# HDMI_RGB_LVDS_fertig_V4.net
KiCad netlist of a schematic drawn in EAGLE
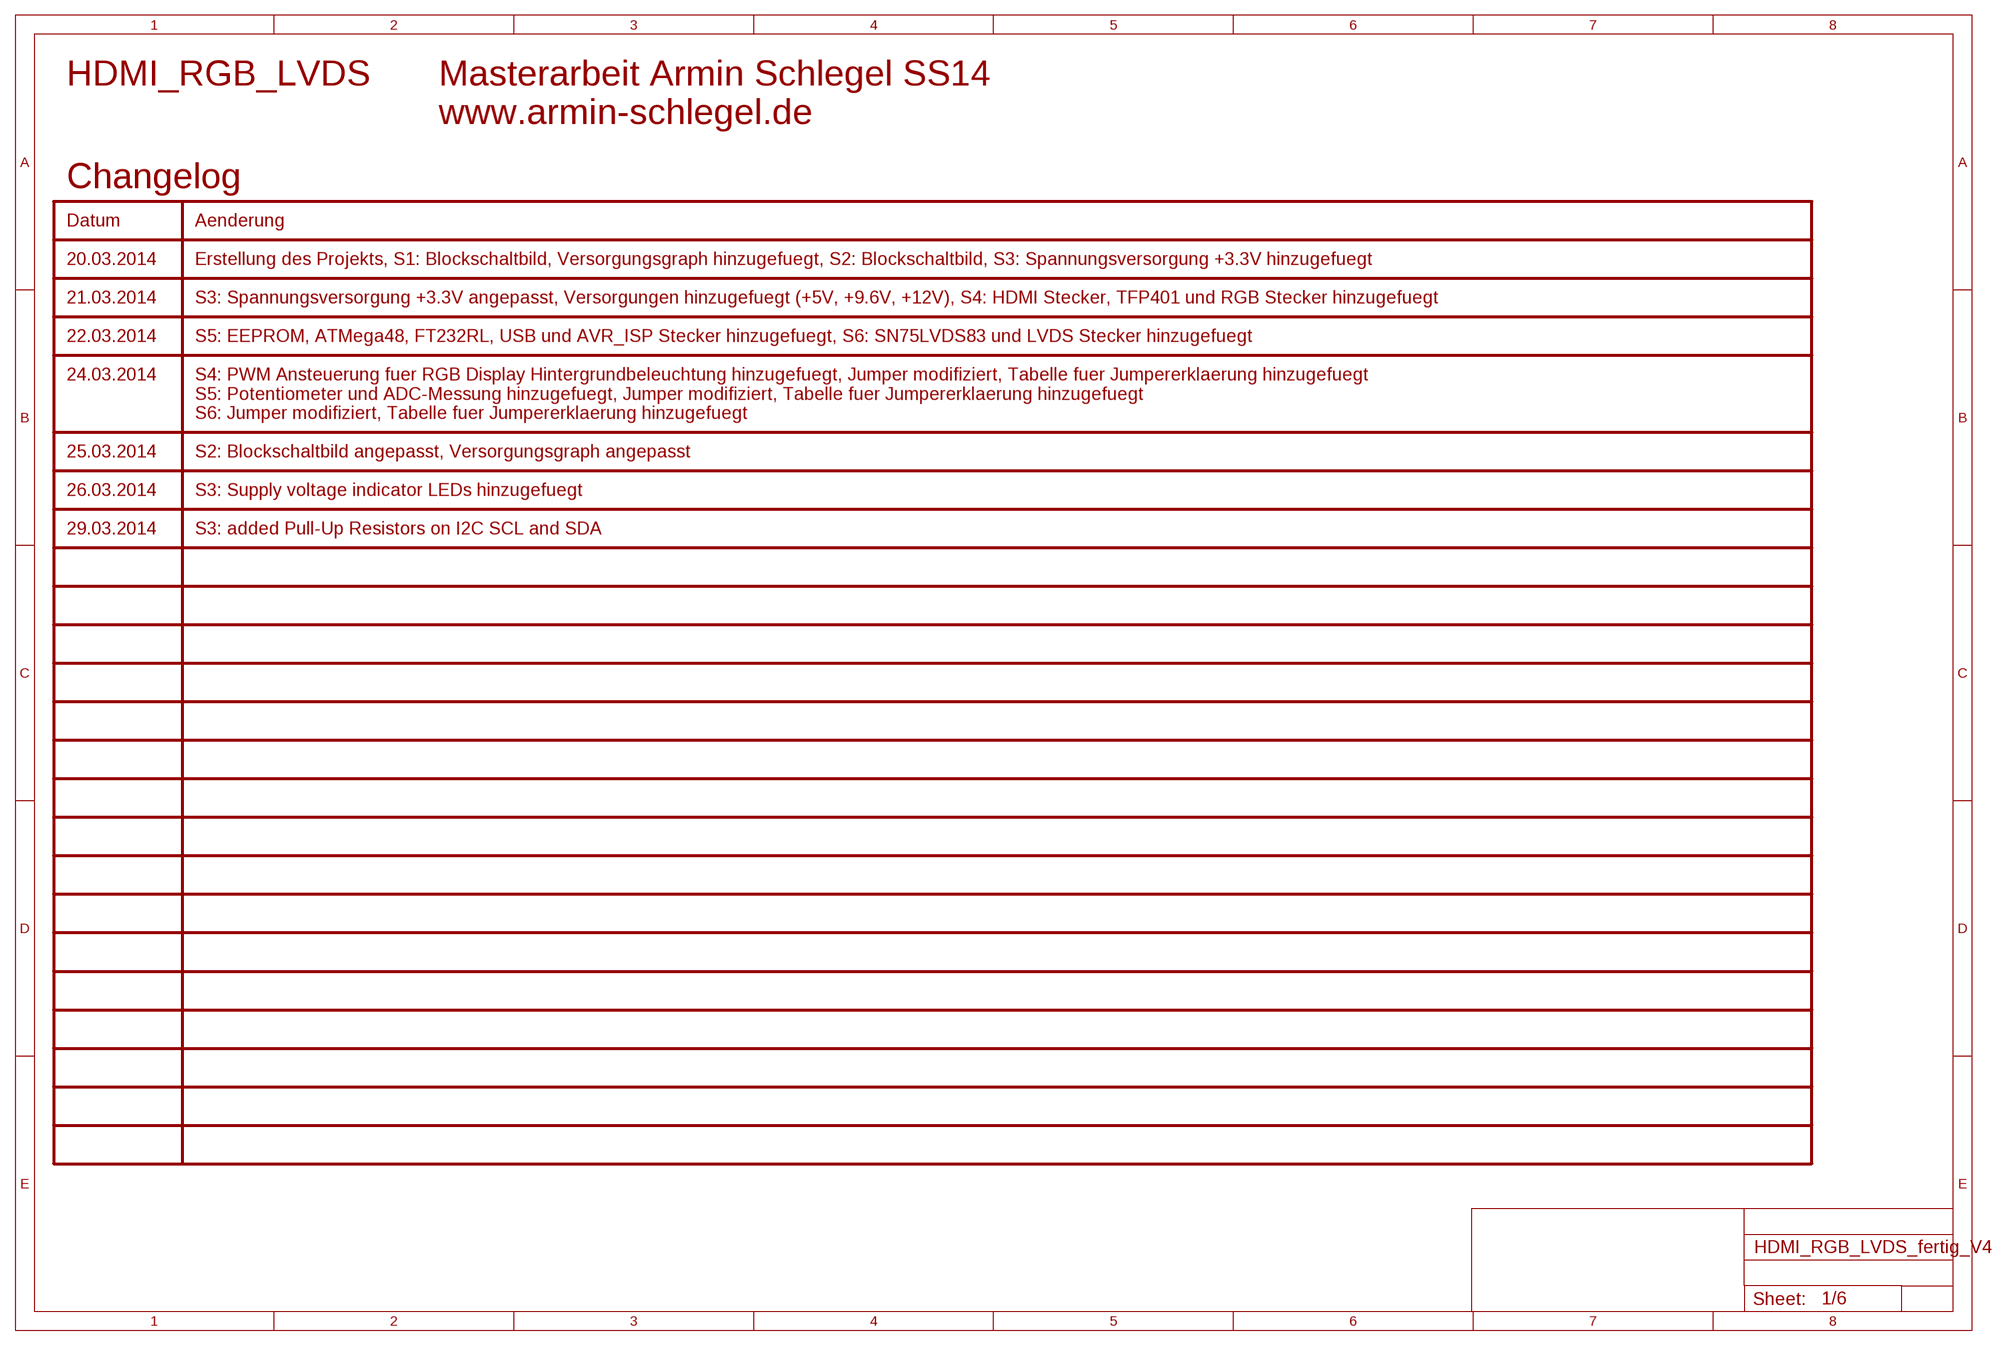
[diagram p0: schematic, sheet 1]
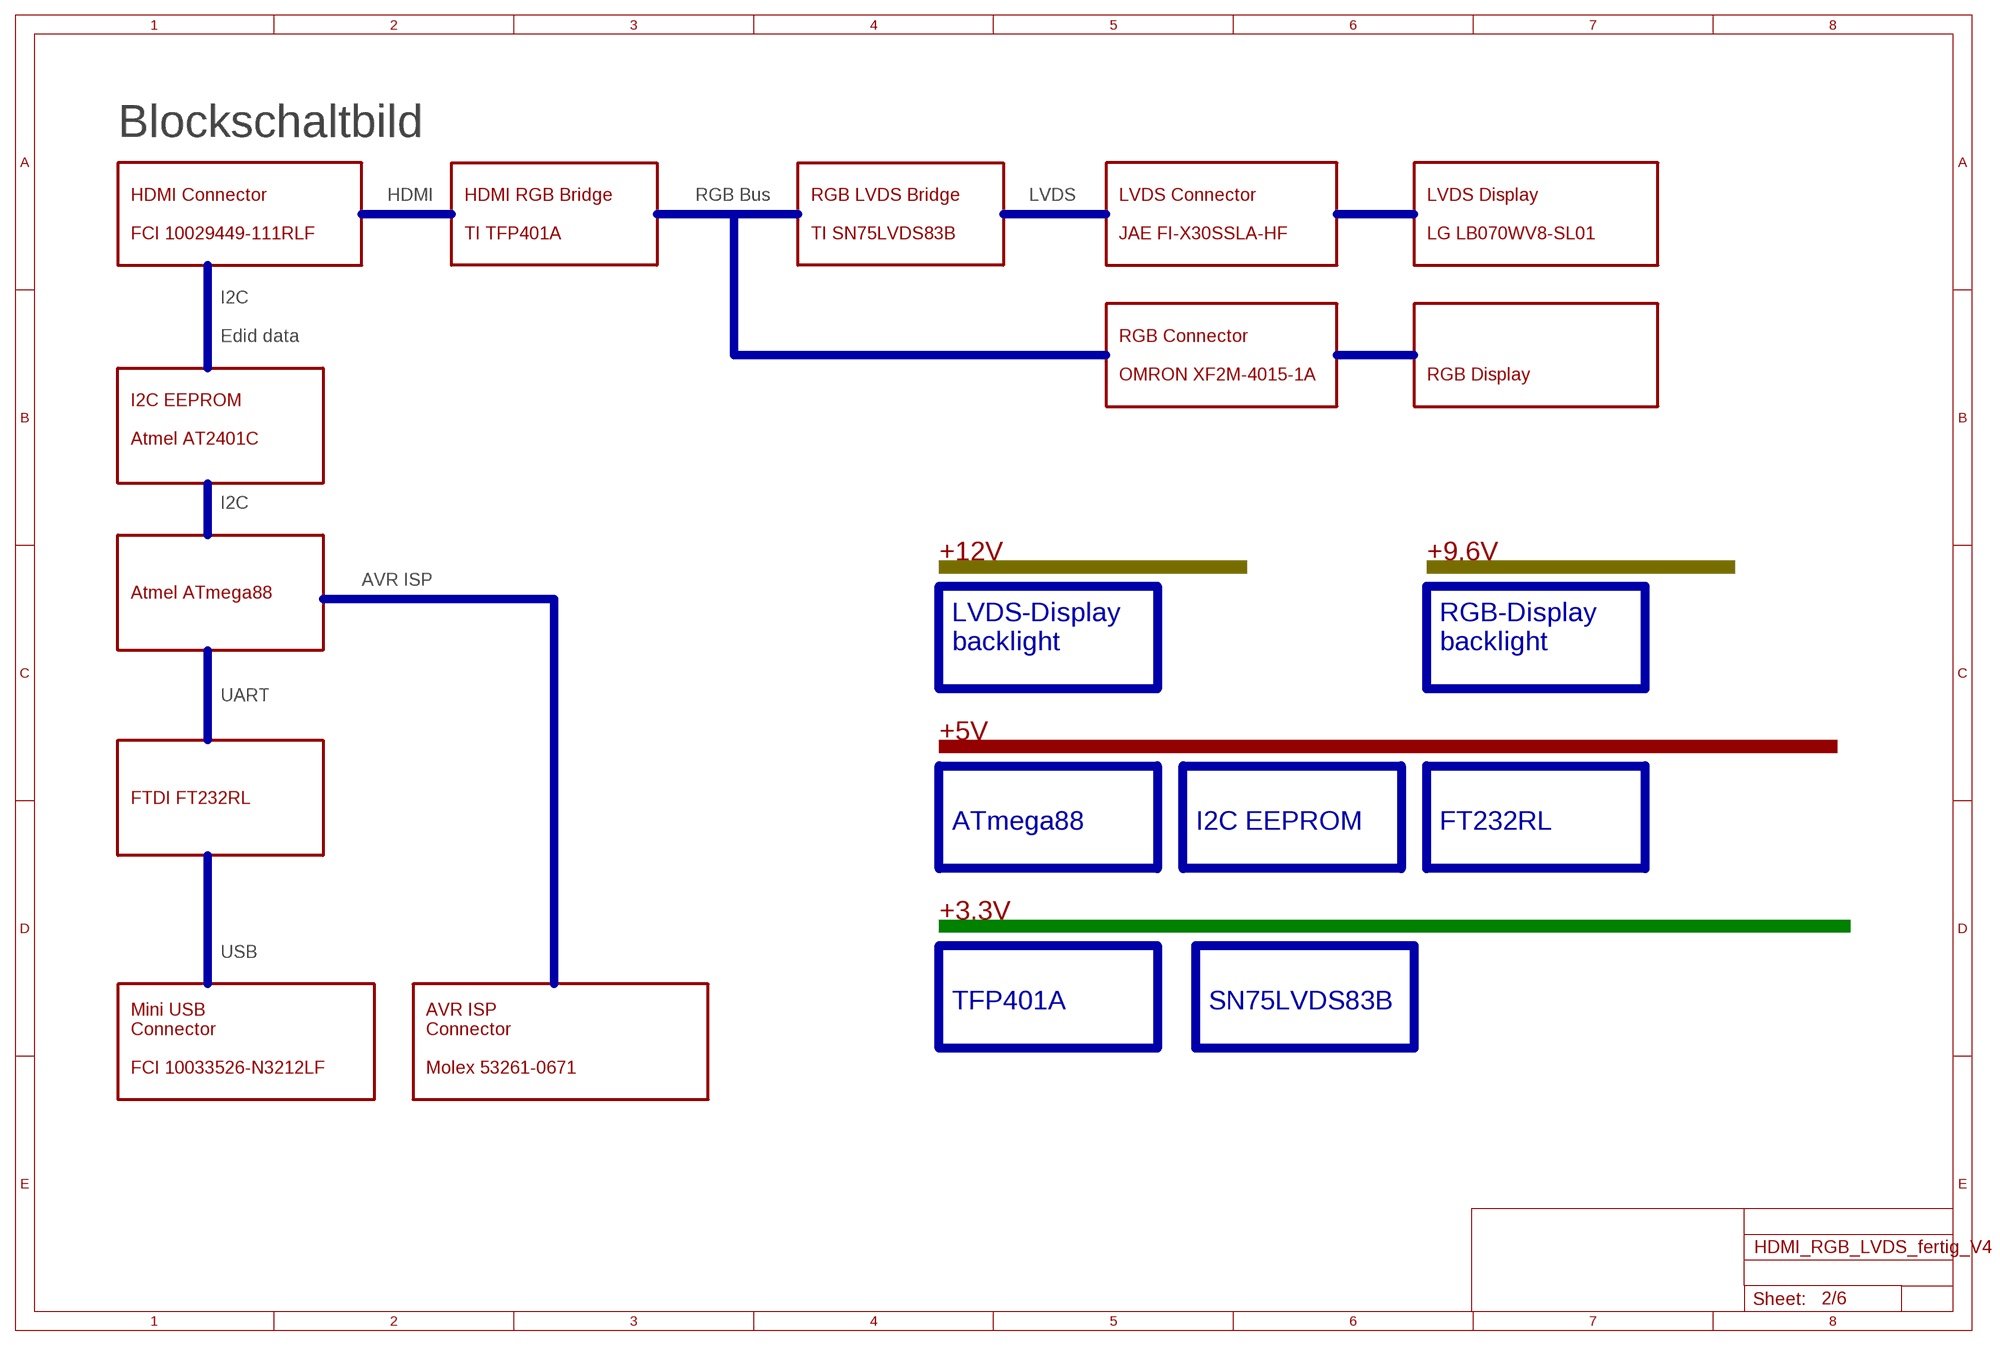
[diagram p1: schematic, sheet 2]
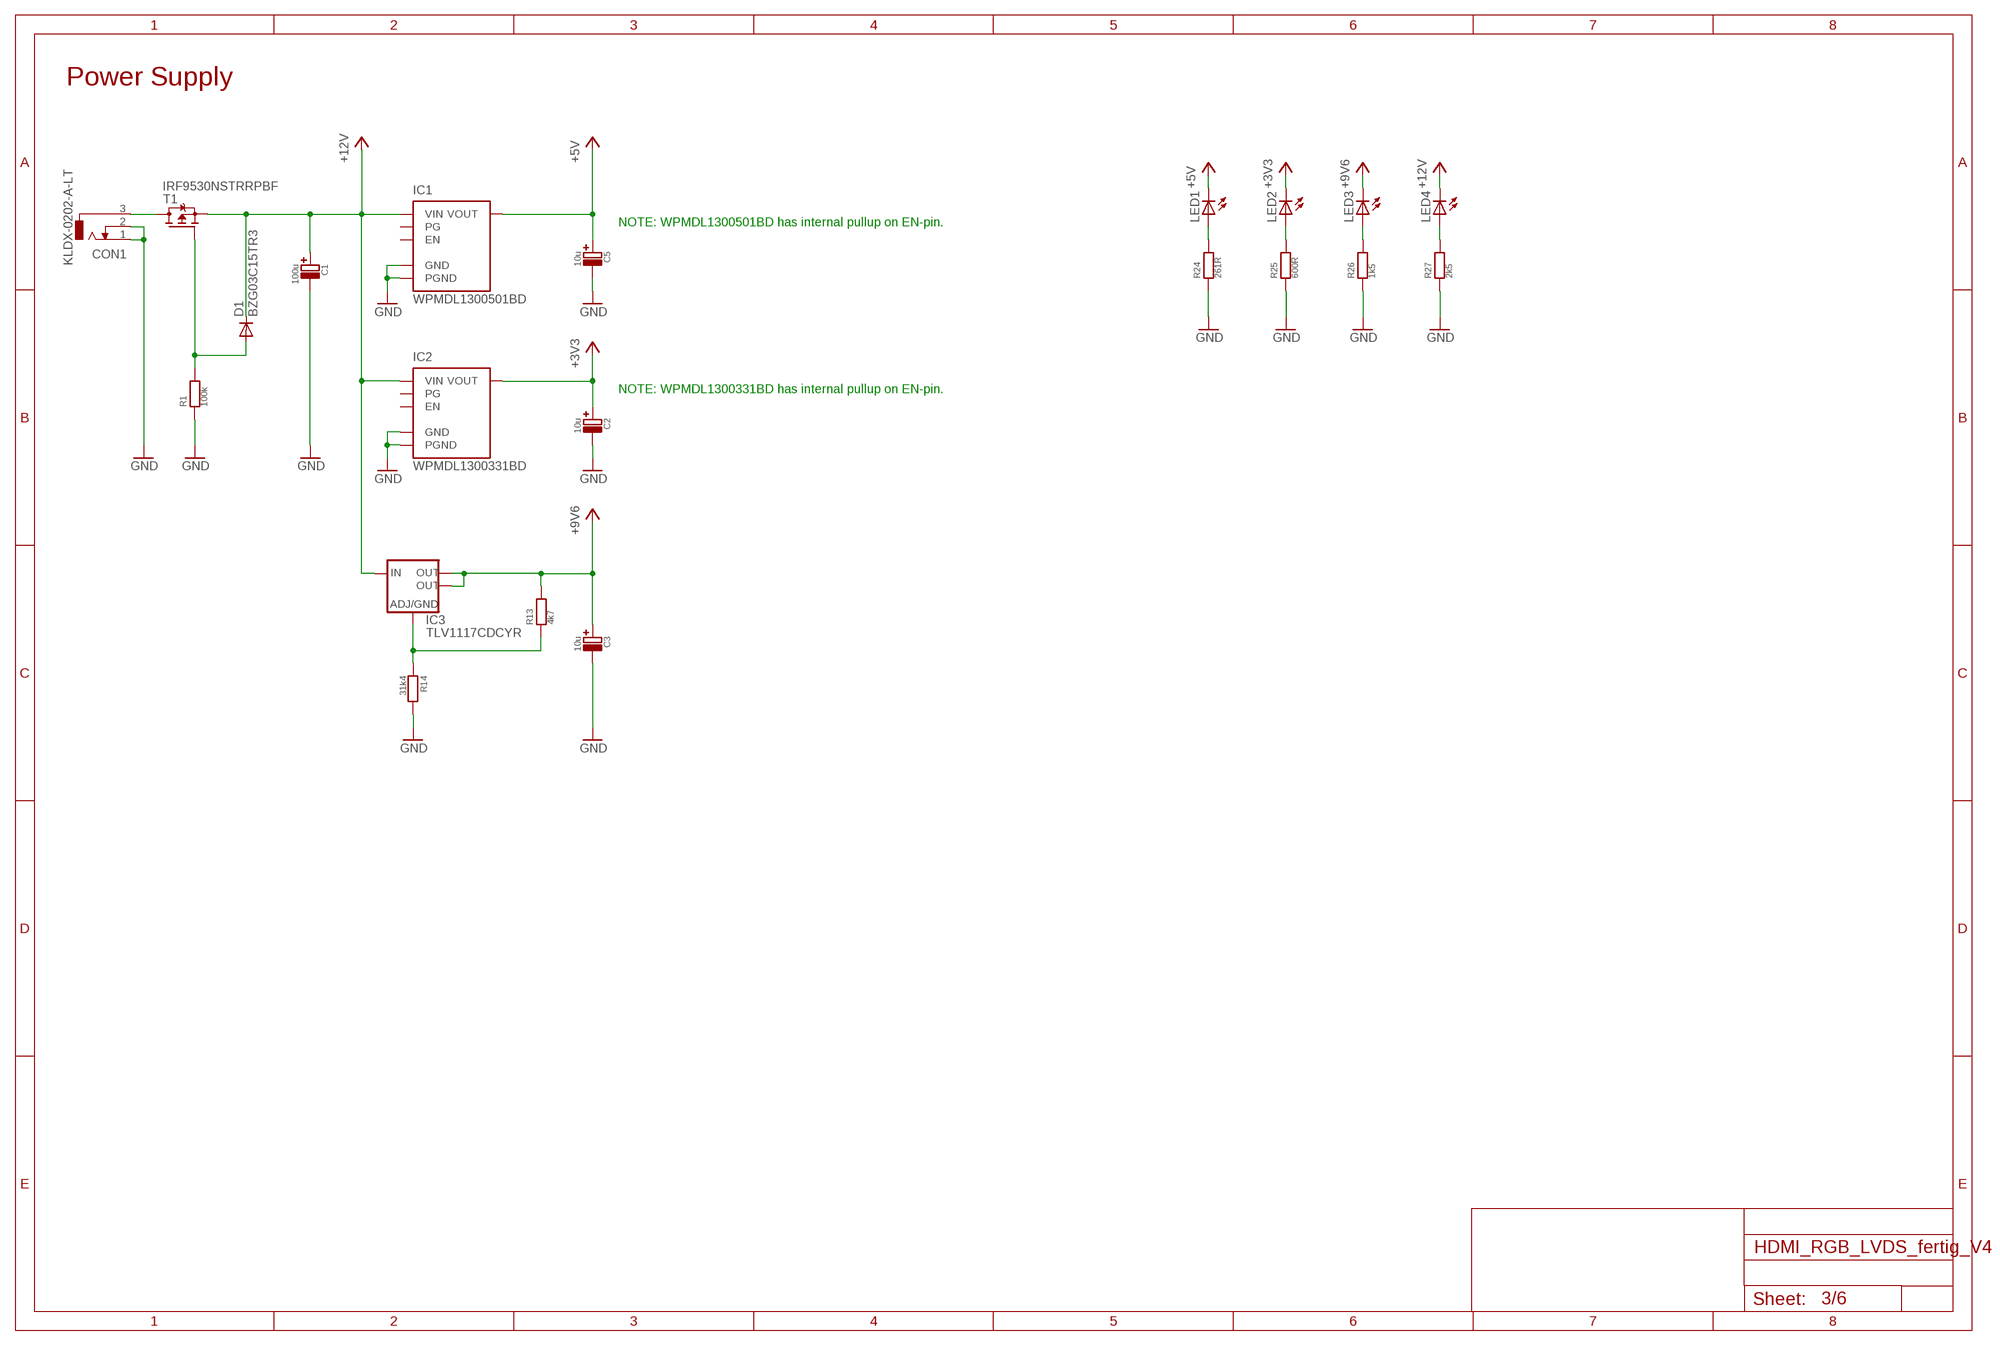
[diagram p2: schematic, sheet 3]
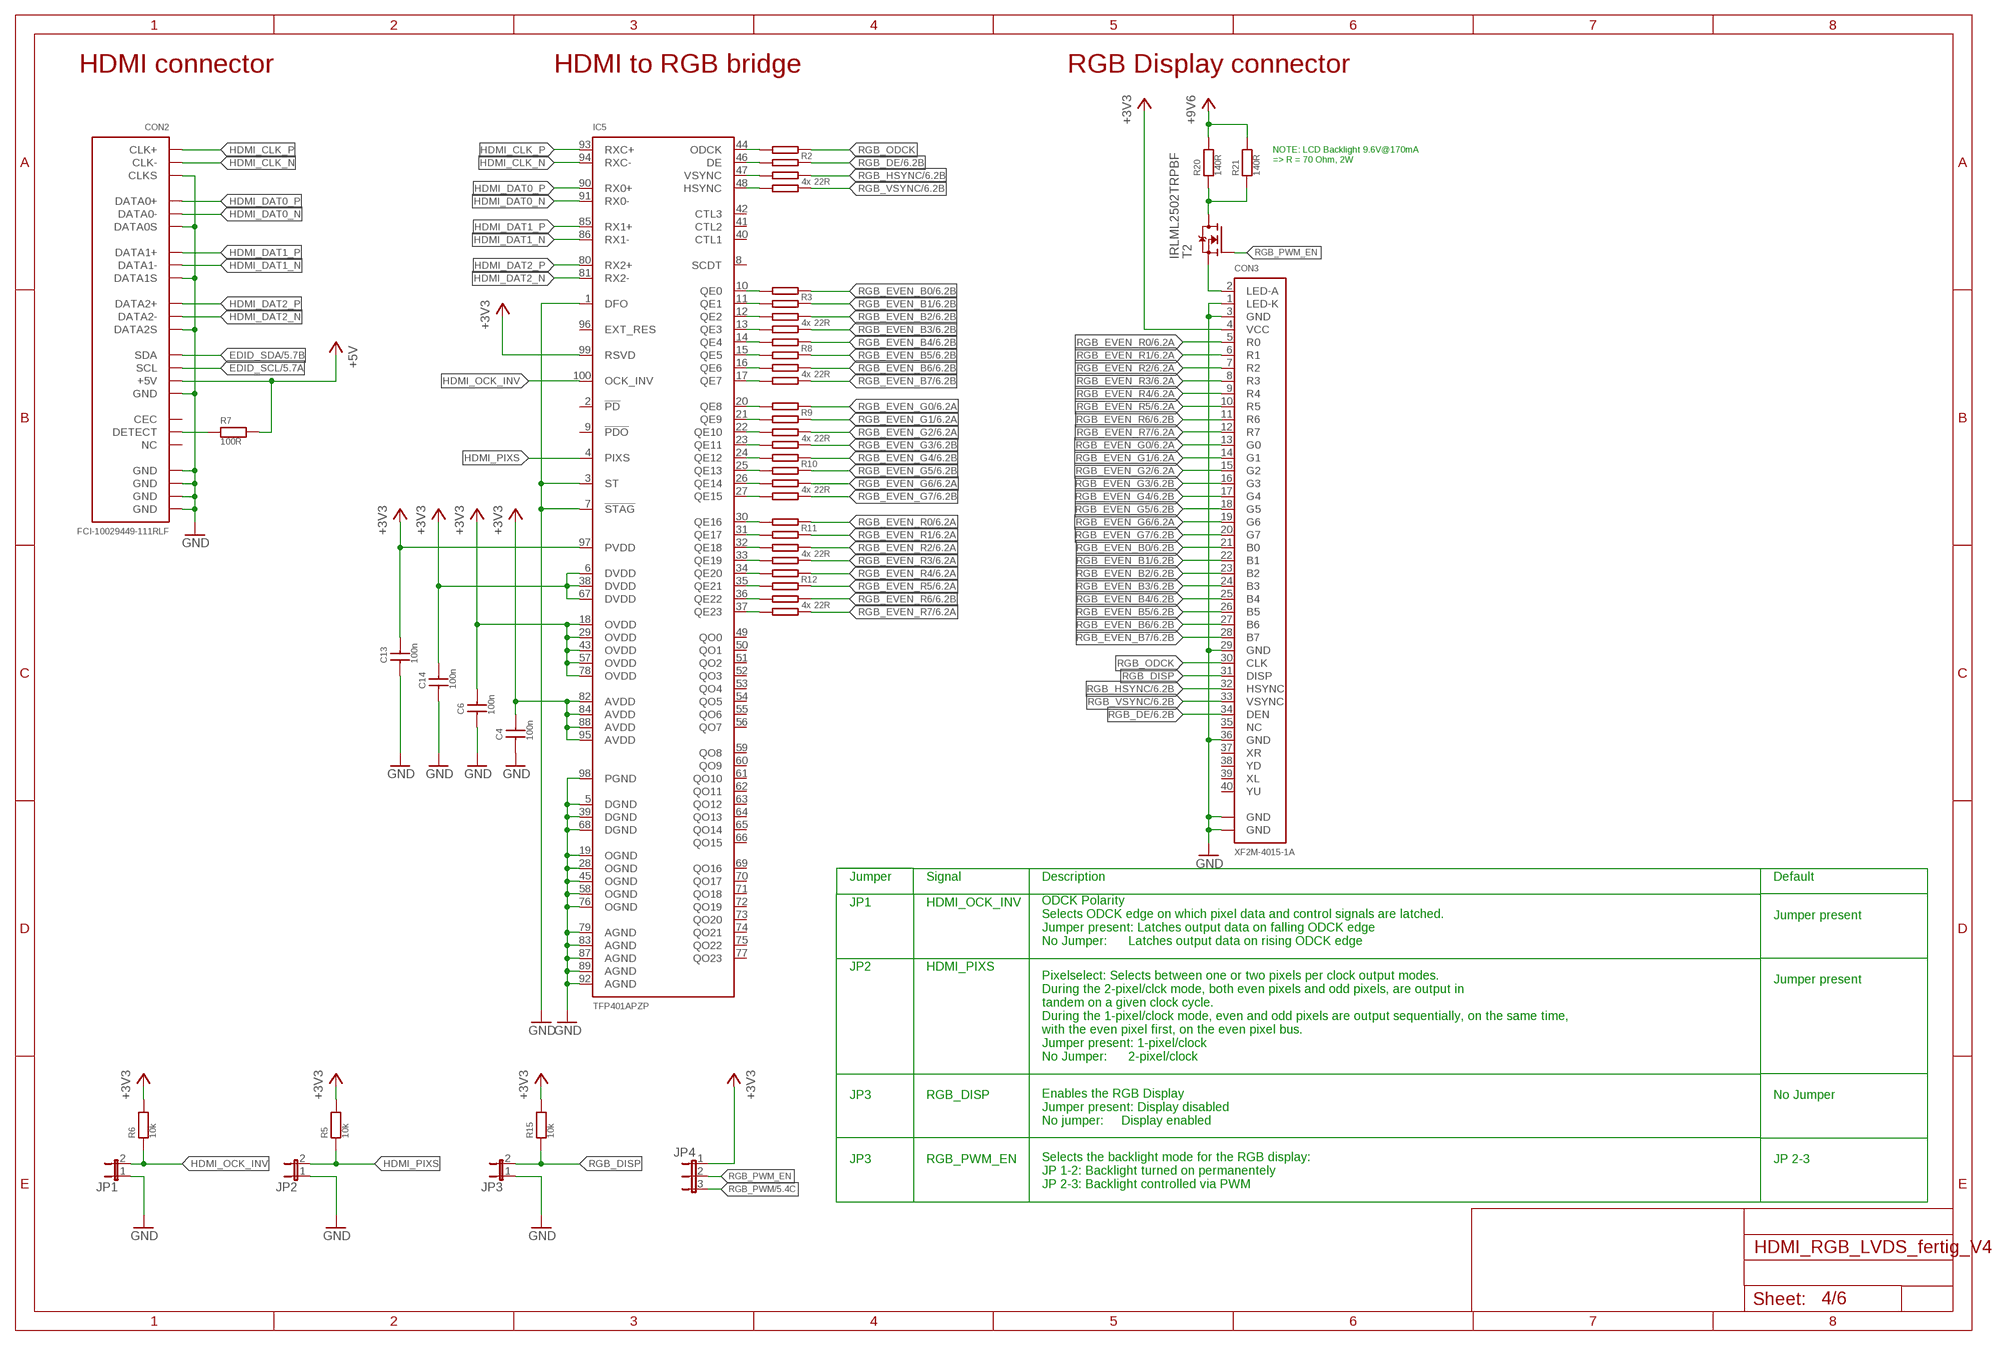
[diagram p3: schematic, sheet 4]
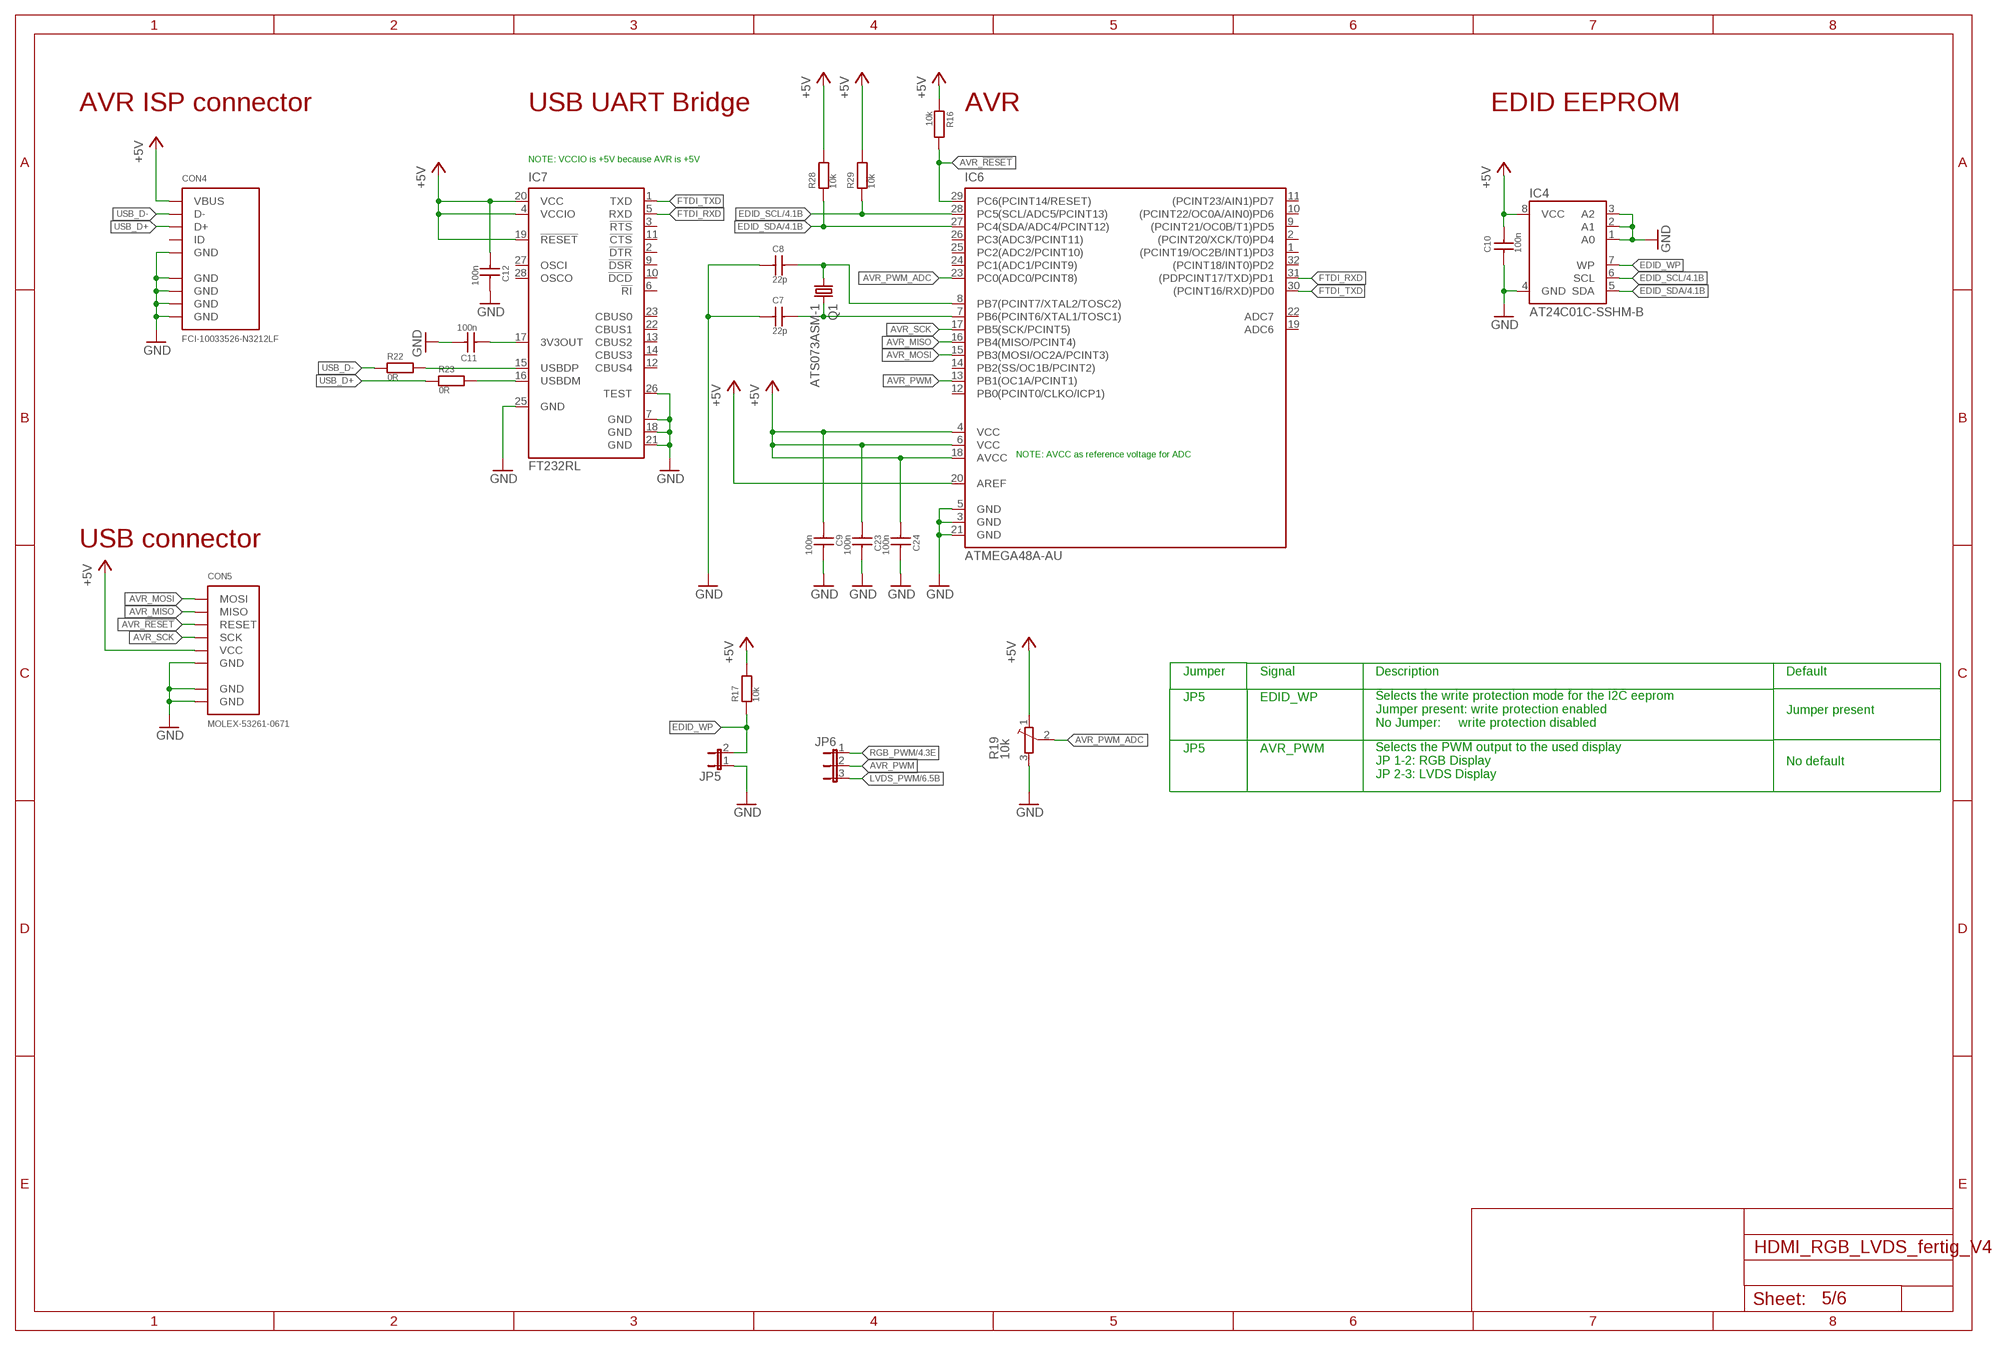
[diagram p4: schematic, sheet 5]
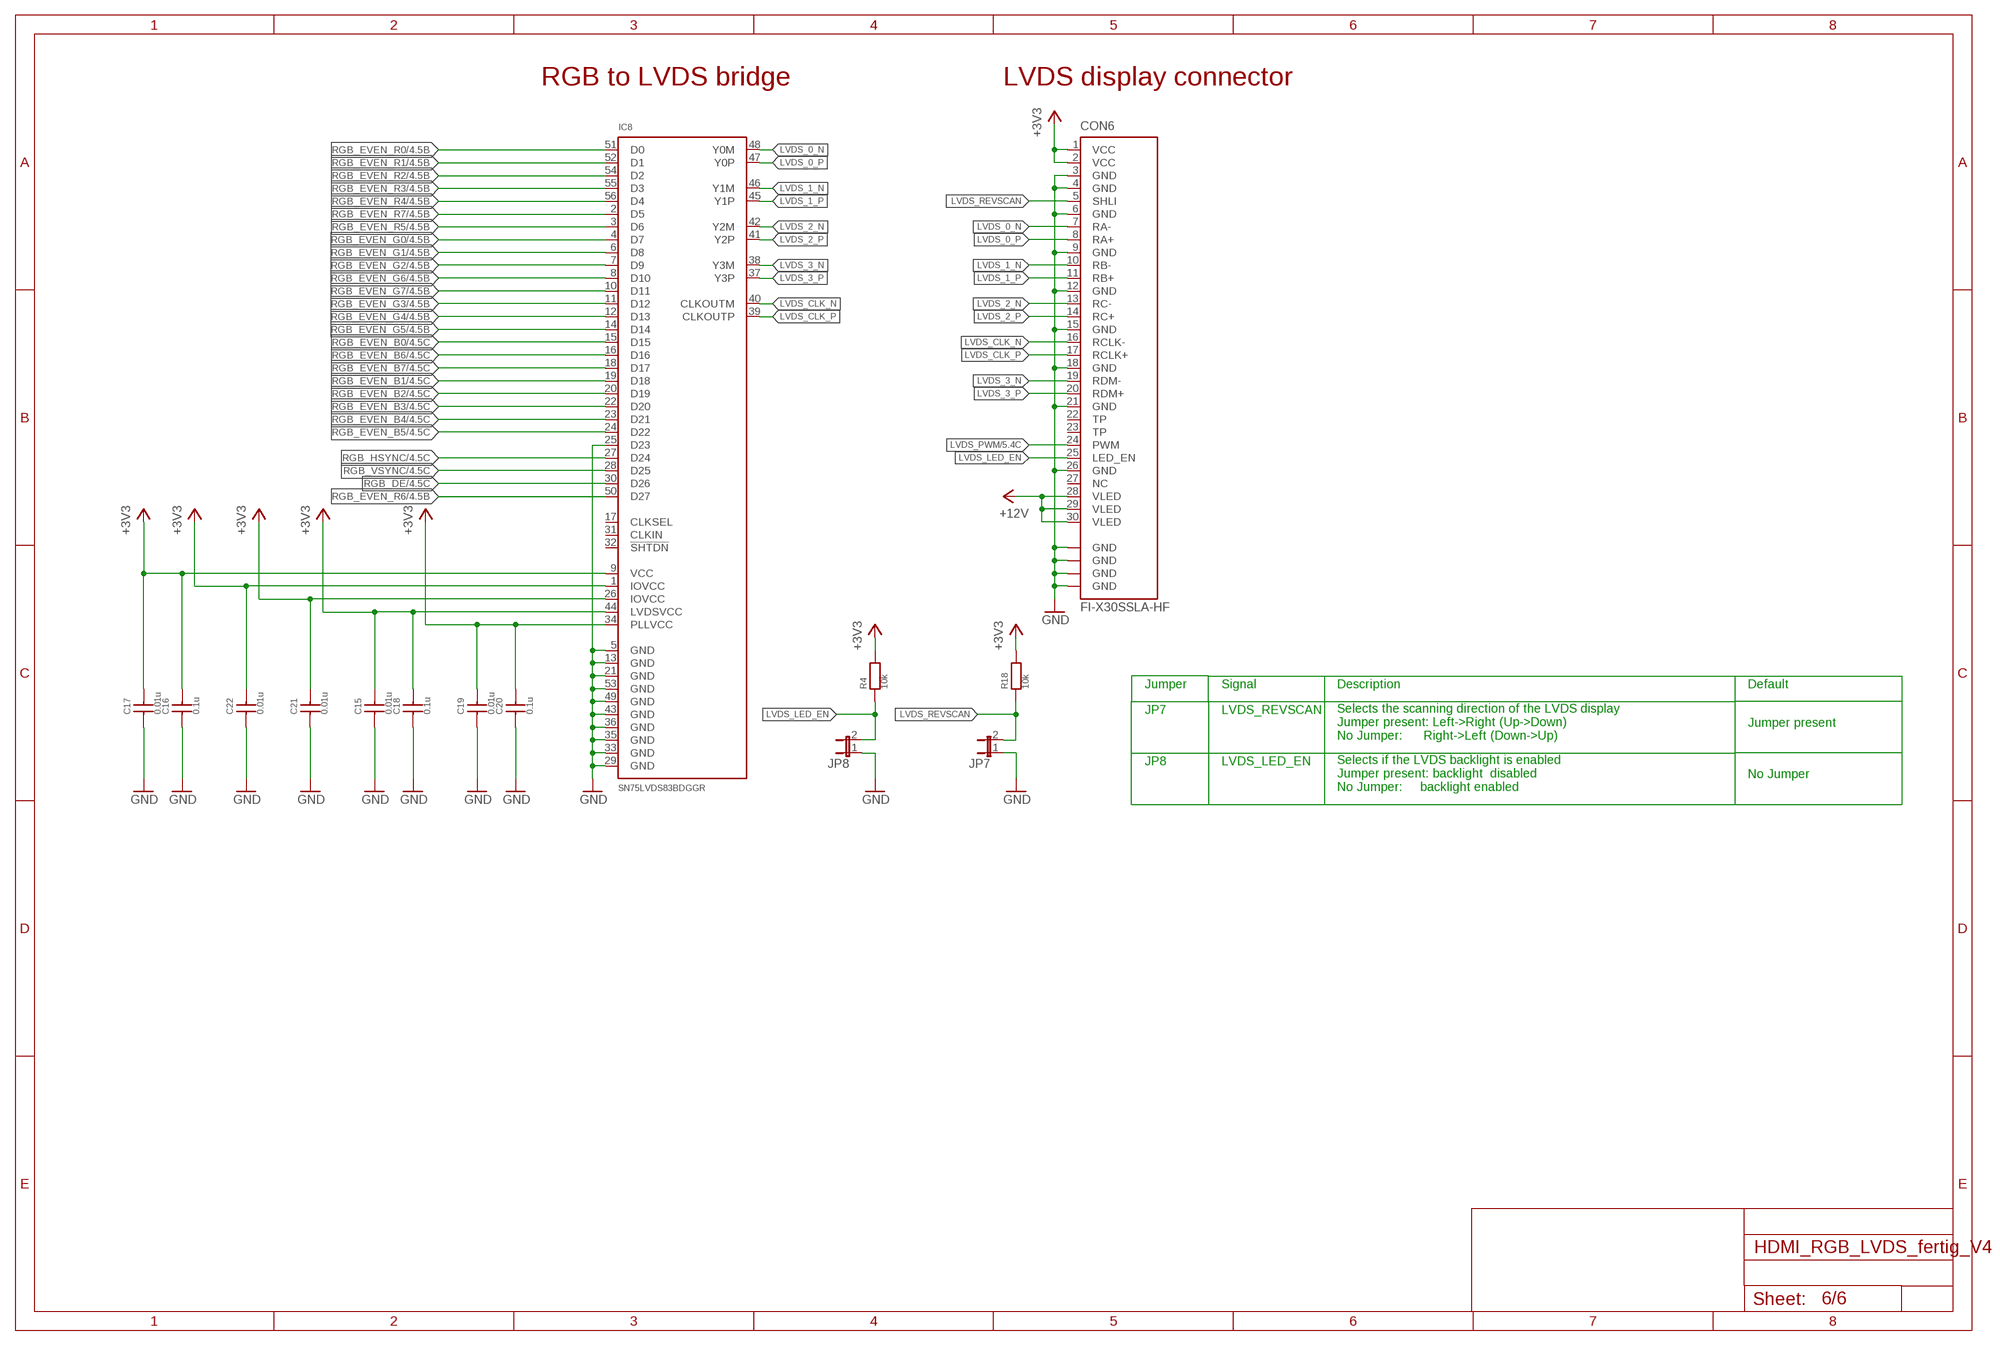
[diagram p5: schematic, sheet 6]

(export (version "E")
  (design (tool "Eeschema 10.0.6"))
  (components
    (comp (ref "C7")
      (value "22p")
      (footprint "eagle-import:C0402")
      (libsource (lib "eagle-import") (part "C_SMD0402"))
    )
    (comp (ref "C8")
      (value "22p")
      (footprint "eagle-import:C0402")
      (libsource (lib "eagle-import") (part "C_SMD0402"))
    )
    (comp (ref "C9")
      (value "100n")
      (footprint "eagle-import:C0402")
      (libsource (lib "eagle-import") (part "C_SMD0402"))
    )
    (comp (ref "C10")
      (value "100n")
      (footprint "eagle-import:C0402")
      (libsource (lib "eagle-import") (part "C_SMD0402"))
    )
    (comp (ref "C11")
      (value "100n")
      (footprint "eagle-import:C0402")
      (libsource (lib "eagle-import") (part "C_SMD0402"))
    )
    (comp (ref "C12")
      (value "100n")
      (footprint "eagle-import:C0402")
      (libsource (lib "eagle-import") (part "C_SMD0402"))
    )
    (comp (ref "C23")
      (value "100n")
      (footprint "eagle-import:C0402")
      (libsource (lib "eagle-import") (part "C_SMD0402"))
    )
    (comp (ref "C24")
      (value "100n")
      (footprint "eagle-import:C0402")
      (libsource (lib "eagle-import") (part "C_SMD0402"))
    )
    (comp (ref "CON4")
      (value "FCI-10033526-N3212LF")
      (footprint "eagle-import:FCI-10033526-N3212LF")
      (libsource (lib "eagle-import") (part "FCI-10033526-N3212LF"))
    )
    (comp (ref "CON5")
      (value "MOLEX-53261-0671")
      (footprint "eagle-import:MOLEX-53261-0671")
      (libsource (lib "eagle-import") (part "MOLEX-53261-0671"))
    )
    (comp (ref "IC4")
      (value "AT24C01C-SSHM-B")
      (footprint "eagle-import:SOIC8")
      (libsource (lib "eagle-import") (part "AT24C01C-SSHM-B"))
    )
    (comp (ref "IC6")
      (value "ATMEGA48A-AU")
      (footprint "eagle-import:TQFP32")
      (libsource (lib "eagle-import") (part "ATMEGA48A-AU"))
    )
    (comp (ref "IC7")
      (value "FT232RL")
      (footprint "eagle-import:SSOP28")
      (libsource (lib "eagle-import") (part "FT232RL"))
    )
    (comp (ref "JP5")
      (value "JUMPER2")
      (footprint "eagle-import:JUMPER2_THROUGHHOLE")
      (libsource (lib "eagle-import") (part "JUMPER2"))
    )
    (comp (ref "JP6")
      (value "JUMPER3")
      (footprint "eagle-import:JUMPER3_THROUGHHOLE")
      (libsource (lib "eagle-import") (part "JUMPER3"))
    )
    (comp (ref "Q1")
      (value "ATS073ASM-1")
      (footprint "eagle-import:HC49_USSM")
      (libsource (lib "eagle-import") (part "ATS073ASM-1"))
    )
    (comp (ref "R16")
      (value "10k")
      (footprint "eagle-import:R0402")
      (libsource (lib "eagle-import") (part "R0402"))
    )
    (comp (ref "R17")
      (value "10k")
      (footprint "eagle-import:R0402")
      (libsource (lib "eagle-import") (part "R0402"))
    )
    (comp (ref "R19")
      (value "10k")
      (footprint "eagle-import:35WR5KLFTR")
      (libsource (lib "eagle-import") (part "35WR5KLFTR"))
    )
    (comp (ref "R22")
      (value "0R")
      (footprint "eagle-import:R0402")
      (libsource (lib "eagle-import") (part "R0402"))
    )
    (comp (ref "R23")
      (value "0R")
      (footprint "eagle-import:R0402")
      (libsource (lib "eagle-import") (part "R0402"))
    )
    (comp (ref "R28")
      (value "10k")
      (footprint "eagle-import:R0402")
      (libsource (lib "eagle-import") (part "R0402"))
    )
    (comp (ref "R29")
      (value "10k")
      (footprint "eagle-import:R0402")
      (libsource (lib "eagle-import") (part "R0402"))
    )
    (comp (ref "U$4")
      (value "FRAME_A3_LANDSCAPE")
      (footprint "eagle-import:FRAME")
      (libsource (lib "eagle-import") (part "FRAME_A3_LANDSCAPE"))
    )
    (comp (ref "C1")
      (value "100u")
      (footprint "eagle-import:C_POL_6X6MM")
      (libsource (lib "eagle-import") (part "RSS1C101MCN1GS"))
    )
    (comp (ref "C2")
      (value "10u")
      (footprint "eagle-import:C_POL_4X4MM")
      (libsource (lib "eagle-import") (part "C_POL4X4MM"))
    )
    (comp (ref "C3")
      (value "10u")
      (footprint "eagle-import:C_POL_4X4MM")
      (libsource (lib "eagle-import") (part "C_POL4X4MM"))
    )
    (comp (ref "C5")
      (value "10u")
      (footprint "eagle-import:C_POL_4X4MM")
      (libsource (lib "eagle-import") (part "C_POL4X4MM"))
    )
    (comp (ref "CON1")
      (value "KLDX-0202-A-LT")
      (footprint "eagle-import:KLDX-0202-A-LT")
      (libsource (lib "eagle-import") (part "KLDX-0202-A-LT"))
    )
    (comp (ref "D1")
      (value "BZG03C15TR3")
      (footprint "eagle-import:DO214A")
      (libsource (lib "eagle-import") (part "BZG03C15TR3"))
    )
    (comp (ref "IC1")
      (value "WPMDL1300501BD")
      (footprint "eagle-import:TO263-5")
      (libsource (lib "eagle-import") (part "WPMDL1300501BD"))
    )
    (comp (ref "IC2")
      (value "WPMDL1300331BD")
      (footprint "eagle-import:TO263-5")
      (libsource (lib "eagle-import") (part "WPMDL1300331BD"))
    )
    (comp (ref "IC3")
      (value "TLV1117CDCYR")
      (footprint "eagle-import:SOT223")
      (libsource (lib "eagle-import") (part "TLV1117CDCYR"))
    )
    (comp (ref "LED1")
      (value "LED0402")
      (footprint "eagle-import:LED0402")
      (libsource (lib "eagle-import") (part "LED0402"))
    )
    (comp (ref "LED2")
      (value "LED0402")
      (footprint "eagle-import:LED0402")
      (libsource (lib "eagle-import") (part "LED0402"))
    )
    (comp (ref "LED3")
      (value "LED0402")
      (footprint "eagle-import:LED0402")
      (libsource (lib "eagle-import") (part "LED0402"))
    )
    (comp (ref "LED4")
      (value "LED0402")
      (footprint "eagle-import:LED0402")
      (libsource (lib "eagle-import") (part "LED0402"))
    )
    (comp (ref "R1")
      (value "100k")
      (footprint "eagle-import:R0402")
      (libsource (lib "eagle-import") (part "R0402"))
    )
    (comp (ref "R13")
      (value "4k7")
      (footprint "eagle-import:R0402")
      (libsource (lib "eagle-import") (part "R0402"))
    )
    (comp (ref "R14")
      (value "31k4")
      (footprint "eagle-import:R0402")
      (libsource (lib "eagle-import") (part "R0402"))
    )
    (comp (ref "R24")
      (value "261R")
      (footprint "eagle-import:R0402")
      (libsource (lib "eagle-import") (part "R0402"))
    )
    (comp (ref "R25")
      (value "600R")
      (footprint "eagle-import:R0402")
      (libsource (lib "eagle-import") (part "R0402"))
    )
    (comp (ref "R26")
      (value "1k5")
      (footprint "eagle-import:R0402")
      (libsource (lib "eagle-import") (part "R0402"))
    )
    (comp (ref "R27")
      (value "2k5")
      (footprint "eagle-import:R0402")
      (libsource (lib "eagle-import") (part "R0402"))
    )
    (comp (ref "T1")
      (value "IRF9530NSTRRPBF")
      (footprint "eagle-import:D2PAK")
      (libsource (lib "eagle-import") (part "IRF9530NSTRRPBF"))
    )
    (comp (ref "U$2")
      (value "FRAME_A3_LANDSCAPE")
      (footprint "eagle-import:FRAME")
      (libsource (lib "eagle-import") (part "FRAME_A3_LANDSCAPE"))
    )
    (comp (ref "U$1")
      (value "FRAME_A3_LANDSCAPE")
      (footprint "eagle-import:FRAME")
      (libsource (lib "eagle-import") (part "FRAME_A3_LANDSCAPE"))
    )
    (comp (ref "C4")
      (value "100n")
      (footprint "eagle-import:C0402")
      (libsource (lib "eagle-import") (part "C_SMD0402"))
    )
    (comp (ref "C6")
      (value "100n")
      (footprint "eagle-import:C0402")
      (libsource (lib "eagle-import") (part "C_SMD0402"))
    )
    (comp (ref "C13")
      (value "100n")
      (footprint "eagle-import:C0402")
      (libsource (lib "eagle-import") (part "C_SMD0402"))
    )
    (comp (ref "C14")
      (value "100n")
      (footprint "eagle-import:C0402")
      (libsource (lib "eagle-import") (part "C_SMD0402"))
    )
    (comp (ref "CON2")
      (value "FCI-10029449-111RLF")
      (footprint "eagle-import:FCI-10029449-111RLF")
      (libsource (lib "eagle-import") (part "FCI-10029449-111RLF"))
    )
    (comp (ref "CON3")
      (value "XF2M-4015-1A")
      (footprint "eagle-import:XF2M-4015-1A")
      (libsource (lib "eagle-import") (part "XF2M-4015-1A"))
    )
    (comp (ref "IC5")
      (value "TFP401APZP")
      (footprint "eagle-import:HTQFP-100")
      (libsource (lib "eagle-import") (part "TFP401APZP"))
    )
    (comp (ref "JP1")
      (value "JUMPER2")
      (footprint "eagle-import:JUMPER2_THROUGHHOLE")
      (libsource (lib "eagle-import") (part "JUMPER2"))
    )
    (comp (ref "JP2")
      (value "JUMPER2")
      (footprint "eagle-import:JUMPER2_THROUGHHOLE")
      (libsource (lib "eagle-import") (part "JUMPER2"))
    )
    (comp (ref "JP3")
      (value "JUMPER2")
      (footprint "eagle-import:JUMPER2_THROUGHHOLE")
      (libsource (lib "eagle-import") (part "JUMPER2"))
    )
    (comp (ref "JP4")
      (value "JUMPER3")
      (footprint "eagle-import:JUMPER3_THROUGHHOLE")
      (libsource (lib "eagle-import") (part "JUMPER3"))
    )
    (comp (ref "R2")
      (value "22R")
      (footprint "eagle-import:R-ARRAY-4X0603")
      (libsource (lib "eagle-import") (part "CTR-742C083220JP-4X22R-4X0603"))
    )
    (comp (ref "R3")
      (value "22R")
      (footprint "eagle-import:R-ARRAY-4X0603")
      (libsource (lib "eagle-import") (part "CTR-742C083220JP-4X22R-4X0603"))
    )
    (comp (ref "R5")
      (value "10k")
      (footprint "eagle-import:R0402")
      (libsource (lib "eagle-import") (part "R0402"))
    )
    (comp (ref "R6")
      (value "10k")
      (footprint "eagle-import:R0402")
      (libsource (lib "eagle-import") (part "R0402"))
    )
    (comp (ref "R7")
      (value "100R")
      (footprint "eagle-import:R0402")
      (libsource (lib "eagle-import") (part "R0402"))
    )
    (comp (ref "R8")
      (value "22R")
      (footprint "eagle-import:R-ARRAY-4X0603")
      (libsource (lib "eagle-import") (part "CTR-742C083220JP-4X22R-4X0603"))
    )
    (comp (ref "R9")
      (value "22R")
      (footprint "eagle-import:R-ARRAY-4X0603")
      (libsource (lib "eagle-import") (part "CTR-742C083220JP-4X22R-4X0603"))
    )
    (comp (ref "R10")
      (value "22R")
      (footprint "eagle-import:R-ARRAY-4X0603")
      (libsource (lib "eagle-import") (part "CTR-742C083220JP-4X22R-4X0603"))
    )
    (comp (ref "R11")
      (value "22R")
      (footprint "eagle-import:R-ARRAY-4X0603")
      (libsource (lib "eagle-import") (part "CTR-742C083220JP-4X22R-4X0603"))
    )
    (comp (ref "R12")
      (value "22R")
      (footprint "eagle-import:R-ARRAY-4X0603")
      (libsource (lib "eagle-import") (part "CTR-742C083220JP-4X22R-4X0603"))
    )
    (comp (ref "R15")
      (value "10k")
      (footprint "eagle-import:R0402")
      (libsource (lib "eagle-import") (part "R0402"))
    )
    (comp (ref "R20")
      (value "140R")
      (footprint "eagle-import:R2512")
      (libsource (lib "eagle-import") (part "R2512"))
    )
    (comp (ref "R21")
      (value "140R")
      (footprint "eagle-import:R2512")
      (libsource (lib "eagle-import") (part "R2512"))
    )
    (comp (ref "T2")
      (value "IRLML2502TRPBF")
      (footprint "eagle-import:SOT23")
      (libsource (lib "eagle-import") (part "IRLML2502TRPBF"))
    )
    (comp (ref "U$3")
      (value "FRAME_A3_LANDSCAPE")
      (footprint "eagle-import:FRAME")
      (libsource (lib "eagle-import") (part "FRAME_A3_LANDSCAPE"))
    )
    (comp (ref "U$15")
      (value "FRAME_A3_LANDSCAPE")
      (footprint "eagle-import:FRAME")
      (libsource (lib "eagle-import") (part "FRAME_A3_LANDSCAPE"))
    )
    (comp (ref "C15")
      (value "0.01u")
      (footprint "eagle-import:C0402")
      (libsource (lib "eagle-import") (part "C_SMD0402"))
    )
    (comp (ref "C16")
      (value "0.1u")
      (footprint "eagle-import:C0402")
      (libsource (lib "eagle-import") (part "C_SMD0402"))
    )
    (comp (ref "C17")
      (value "0.01u")
      (footprint "eagle-import:C0402")
      (libsource (lib "eagle-import") (part "C_SMD0402"))
    )
    (comp (ref "C18")
      (value "0.1u")
      (footprint "eagle-import:C0402")
      (libsource (lib "eagle-import") (part "C_SMD0402"))
    )
    (comp (ref "C19")
      (value "0.01u")
      (footprint "eagle-import:C0402")
      (libsource (lib "eagle-import") (part "C_SMD0402"))
    )
    (comp (ref "C20")
      (value "0.1u")
      (footprint "eagle-import:C0402")
      (libsource (lib "eagle-import") (part "C_SMD0402"))
    )
    (comp (ref "C21")
      (value "0.01u")
      (footprint "eagle-import:C0402")
      (libsource (lib "eagle-import") (part "C_SMD0402"))
    )
    (comp (ref "C22")
      (value "0.01u")
      (footprint "eagle-import:C0402")
      (libsource (lib "eagle-import") (part "C_SMD0402"))
    )
    (comp (ref "CON6")
      (value "FI-X30SSLA-HF")
      (footprint "eagle-import:FI-X30SSLA-HF")
      (libsource (lib "eagle-import") (part "FI-X30SSLA-HF"))
    )
    (comp (ref "IC8")
      (value "SN75LVDS83BDGGR")
      (footprint "eagle-import:TSSOP-56")
      (libsource (lib "eagle-import") (part "SN75LVDS83BDGGR"))
    )
    (comp (ref "JP7")
      (value "JUMPER2")
      (footprint "eagle-import:JUMPER2_THROUGHHOLE")
      (libsource (lib "eagle-import") (part "JUMPER2"))
    )
    (comp (ref "JP8")
      (value "JUMPER2")
      (footprint "eagle-import:JUMPER2_THROUGHHOLE")
      (libsource (lib "eagle-import") (part "JUMPER2"))
    )
    (comp (ref "R4")
      (value "10k")
      (footprint "eagle-import:R0402")
      (libsource (lib "eagle-import") (part "R0402"))
    )
    (comp (ref "R18")
      (value "10k")
      (footprint "eagle-import:R0402")
      (libsource (lib "eagle-import") (part "R0402"))
    )
    (comp (ref "U$5")
      (value "FRAME_A3_LANDSCAPE")
      (footprint "eagle-import:FRAME")
      (libsource (lib "eagle-import") (part "FRAME_A3_LANDSCAPE"))
    )
  )
  (nets
    (net (code "3") (name "+3V3") (class "Default")
      (node (ref "C13") (pin "2") (pinfunction "P$2_2") (pintype "passive"))
      (node (ref "C14") (pin "2") (pinfunction "P$2_2") (pintype "passive"))
      (node (ref "C15") (pin "2") (pinfunction "P$2_2") (pintype "passive"))
      (node (ref "C16") (pin "2") (pinfunction "P$2_2") (pintype "passive"))
      (node (ref "C17") (pin "2") (pinfunction "P$2_2") (pintype "passive"))
      (node (ref "C18") (pin "2") (pinfunction "P$2_2") (pintype "passive"))
      (node (ref "C19") (pin "2") (pinfunction "P$2_2") (pintype "passive"))
      (node (ref "C2") (pin "+") (pinfunction "+_+") (pintype "passive"))
      (node (ref "C20") (pin "2") (pinfunction "P$2_2") (pintype "passive"))
      (node (ref "C21") (pin "2") (pinfunction "P$2_2") (pintype "passive"))
      (node (ref "C22") (pin "2") (pinfunction "P$2_2") (pintype "passive"))
      (node (ref "C4") (pin "2") (pinfunction "P$2_2") (pintype "passive"))
      (node (ref "C6") (pin "2") (pinfunction "P$2_2") (pintype "passive"))
      (node (ref "CON3") (pin "4") (pinfunction "VCC_4") (pintype "bidirectional"))
      (node (ref "CON6") (pin "1") (pinfunction "VCC_1") (pintype "bidirectional"))
      (node (ref "CON6") (pin "2") (pinfunction "VCC_2") (pintype "bidirectional"))
      (node (ref "IC2") (pin "3") (pinfunction "VOUT_3") (pintype "bidirectional"))
      (node (ref "IC5") (pin "18") (pinfunction "OVDD_18") (pintype "power_in"))
      (node (ref "IC5") (pin "29") (pinfunction "OVDD_29") (pintype "power_in"))
      (node (ref "IC5") (pin "38") (pinfunction "DVDD_38") (pintype "power_in"))
      (node (ref "IC5") (pin "43") (pinfunction "OVDD_43") (pintype "power_in"))
      (node (ref "IC5") (pin "57") (pinfunction "OVDD_57") (pintype "power_in"))
      (node (ref "IC5") (pin "6") (pinfunction "DVDD_6") (pintype "power_in"))
      (node (ref "IC5") (pin "67") (pinfunction "DVDD_67") (pintype "power_in"))
      (node (ref "IC5") (pin "78") (pinfunction "OVDD_78") (pintype "power_in"))
      (node (ref "IC5") (pin "82") (pinfunction "AVDD_82") (pintype "power_in"))
      (node (ref "IC5") (pin "84") (pinfunction "AVDD_84") (pintype "power_in"))
      (node (ref "IC5") (pin "88") (pinfunction "AVDD_88") (pintype "power_in"))
      (node (ref "IC5") (pin "95") (pinfunction "AVDD_95") (pintype "power_in"))
      (node (ref "IC5") (pin "97") (pinfunction "PVDD_97") (pintype "power_in"))
      (node (ref "IC5") (pin "99") (pinfunction "RSVD_99") (pintype "bidirectional"))
      (node (ref "IC8") (pin "1") (pinfunction "IOVCC_1") (pintype "power_in"))
      (node (ref "IC8") (pin "26") (pinfunction "IOVCC_26") (pintype "power_in"))
      (node (ref "IC8") (pin "34") (pinfunction "PLLVCC_34") (pintype "power_in"))
      (node (ref "IC8") (pin "44") (pinfunction "LVDSVCC_44") (pintype "power_in"))
      (node (ref "IC8") (pin "9") (pinfunction "VCC_9") (pintype "power_in"))
      (node (ref "JP4") (pin "1") (pinfunction "1_1") (pintype "passive"))
      (node (ref "LED2") (pin "C") (pinfunction "C_C") (pintype "passive"))
      (node (ref "R15") (pin "2") (pinfunction "P$2_2") (pintype "passive"))
      (node (ref "R18") (pin "2") (pinfunction "P$2_2") (pintype "passive"))
      (node (ref "R4") (pin "2") (pinfunction "P$2_2") (pintype "passive"))
      (node (ref "R5") (pin "2") (pinfunction "P$2_2") (pintype "passive"))
      (node (ref "R6") (pin "2") (pinfunction "P$2_2") (pintype "passive"))
    )
    (net (code "4") (name "+5V") (class "Default")
      (node (ref "C10") (pin "2") (pinfunction "P$2_2") (pintype "passive"))
      (node (ref "C12") (pin "1") (pinfunction "P$1_1") (pintype "passive"))
      (node (ref "C23") (pin "1") (pinfunction "P$1_1") (pintype "passive"))
      (node (ref "C24") (pin "1") (pinfunction "P$1_1") (pintype "passive"))
      (node (ref "C5") (pin "+") (pinfunction "+_+") (pintype "passive"))
      (node (ref "C9") (pin "1") (pinfunction "P$1_1") (pintype "passive"))
      (node (ref "CON2") (pin "18") (pinfunction "+5V_18") (pintype "bidirectional"))
      (node (ref "CON4") (pin "1") (pinfunction "VBUS_1") (pintype "bidirectional"))
      (node (ref "CON5") (pin "5") (pinfunction "VCC_5") (pintype "bidirectional"))
      (node (ref "IC1") (pin "3") (pinfunction "VOUT_3") (pintype "bidirectional"))
      (node (ref "IC4") (pin "8") (pinfunction "VCC_8") (pintype "power_in"))
      (node (ref "IC6") (pin "18") (pinfunction "AVCC_18") (pintype "power_in"))
      (node (ref "IC6") (pin "20") (pinfunction "AREF_20") (pintype "power_in"))
      (node (ref "IC6") (pin "4") (pinfunction "VCC_4") (pintype "power_in"))
      (node (ref "IC6") (pin "6") (pinfunction "VCC_6") (pintype "power_in"))
      (node (ref "IC7") (pin "19") (pinfunction "~{RESET}_19") (pintype "input"))
      (node (ref "IC7") (pin "20") (pinfunction "VCC_20") (pintype "power_in"))
      (node (ref "IC7") (pin "4") (pinfunction "VCCIO_4") (pintype "power_in"))
      (node (ref "LED1") (pin "C") (pinfunction "C_C") (pintype "passive"))
      (node (ref "R16") (pin "1") (pinfunction "P$1_1") (pintype "passive"))
      (node (ref "R17") (pin "2") (pinfunction "P$2_2") (pintype "passive"))
      (node (ref "R19") (pin "1") (pinfunction "E_1") (pintype "passive"))
      (node (ref "R28") (pin "2") (pinfunction "P$2_2") (pintype "passive"))
      (node (ref "R29") (pin "2") (pinfunction "P$2_2") (pintype "passive"))
      (node (ref "R7") (pin "2") (pinfunction "P$2_2") (pintype "passive"))
    )
    (net (code "5") (name "+9V6") (class "Default")
      (node (ref "C3") (pin "+") (pinfunction "+_+") (pintype "passive"))
      (node (ref "IC3") (pin "2") (pinfunction "OUT_2") (pintype "passive"))
      (node (ref "IC3") (pin "4") (pinfunction "OUT1_4") (pintype "passive"))
      (node (ref "LED3") (pin "C") (pinfunction "C_C") (pintype "passive"))
      (node (ref "R13") (pin "2") (pinfunction "P$2_2") (pintype "passive"))
      (node (ref "R20") (pin "2") (pinfunction "P$2_2") (pintype "passive"))
      (node (ref "R21") (pin "2") (pinfunction "P$2_2") (pintype "passive"))
    )
    (net (code "6") (name "+12V") (class "Default")
      (node (ref "C1") (pin "+") (pinfunction "+_+") (pintype "passive"))
      (node (ref "CON6") (pin "28") (pinfunction "VLED_28") (pintype "bidirectional"))
      (node (ref "CON6") (pin "29") (pinfunction "VLED_29") (pintype "bidirectional"))
      (node (ref "CON6") (pin "30") (pinfunction "VLED_30") (pintype "bidirectional"))
      (node (ref "D1") (pin "C") (pinfunction "C_C") (pintype "passive"))
      (node (ref "IC1") (pin "1") (pinfunction "VIN_1") (pintype "bidirectional"))
      (node (ref "IC2") (pin "1") (pinfunction "VIN_1") (pintype "bidirectional"))
      (node (ref "IC3") (pin "3") (pinfunction "IN_3") (pintype "input"))
      (node (ref "LED4") (pin "C") (pinfunction "C_C") (pintype "passive"))
      (node (ref "T1") (pin "3") (pinfunction "S_3") (pintype "passive"))
    )
    (net (code "9") (name "AVR_MISO") (class "Default")
      (node (ref "CON5") (pin "2") (pinfunction "MISO_2") (pintype "bidirectional"))
      (node (ref "IC6") (pin "16") (pinfunction "PB4(MISO/PCINT4)_16") (pintype "bidirectional"))
    )
    (net (code "10") (name "AVR_MOSI") (class "Default")
      (node (ref "CON5") (pin "1") (pinfunction "MOSI_1") (pintype "bidirectional"))
      (node (ref "IC6") (pin "15") (pinfunction "PB3(MOSI/OC2A/PCINT3)_15") (pintype "bidirectional"))
    )
    (net (code "11") (name "AVR_PWM") (class "Default")
      (node (ref "IC6") (pin "13") (pinfunction "PB1(OC1A/PCINT1)_13") (pintype "bidirectional"))
      (node (ref "JP6") (pin "2") (pinfunction "2_2") (pintype "passive"))
    )
    (net (code "12") (name "AVR_PWM_ADC") (class "Default")
      (node (ref "IC6") (pin "23") (pinfunction "PC0(ADC0/PCINT8)_23") (pintype "bidirectional"))
      (node (ref "R19") (pin "2") (pinfunction "S_2") (pintype "passive"))
    )
    (net (code "13") (name "AVR_SCK") (class "Default")
      (node (ref "CON5") (pin "4") (pinfunction "SCK_4") (pintype "bidirectional"))
      (node (ref "IC6") (pin "17") (pinfunction "PB5(SCK/PCINT5)_17") (pintype "bidirectional"))
    )
    (net (code "14") (name "AVR_~{RESET}") (class "Default")
      (node (ref "CON5") (pin "3") (pinfunction "RESET_3") (pintype "bidirectional"))
      (node (ref "IC6") (pin "29") (pinfunction "PC6(PCINT14/RESET)_29") (pintype "bidirectional"))
      (node (ref "R16") (pin "2") (pinfunction "P$2_2") (pintype "passive"))
    )
    (net (code "15") (name "EDID_SCL") (class "Default")
      (node (ref "CON2") (pin "15") (pinfunction "SCL_15") (pintype "bidirectional"))
      (node (ref "IC4") (pin "6") (pinfunction "SCL_6") (pintype "bidirectional"))
      (node (ref "IC6") (pin "28") (pinfunction "PC5(SCL/ADC5/PCINT13)_28") (pintype "bidirectional"))
      (node (ref "R29") (pin "1") (pinfunction "P$1_1") (pintype "passive"))
    )
    (net (code "16") (name "EDID_SDA") (class "Default")
      (node (ref "CON2") (pin "16") (pinfunction "SDA_16") (pintype "bidirectional"))
      (node (ref "IC4") (pin "5") (pinfunction "SDA_5") (pintype "bidirectional"))
      (node (ref "IC6") (pin "27") (pinfunction "PC4(SDA/ADC4/PCINT12)_27") (pintype "bidirectional"))
      (node (ref "R28") (pin "1") (pinfunction "P$1_1") (pintype "passive"))
    )
    (net (code "17") (name "EDID_WP") (class "Default")
      (node (ref "IC4") (pin "7") (pinfunction "WP_7") (pintype "input"))
      (node (ref "JP5") (pin "2") (pinfunction "2_2") (pintype "passive"))
      (node (ref "R17") (pin "1") (pinfunction "P$1_1") (pintype "passive"))
    )
    (net (code "18") (name "FTDI_RXD") (class "Default")
      (node (ref "IC6") (pin "31") (pinfunction "(PDPCINT17/TXD)PD1_31") (pintype "bidirectional"))
      (node (ref "IC7") (pin "5") (pinfunction "RXD_5") (pintype "input"))
    )
    (net (code "19") (name "FTDI_TXD") (class "Default")
      (node (ref "IC6") (pin "30") (pinfunction "(PCINT16/RXD)PD0_30") (pintype "bidirectional"))
      (node (ref "IC7") (pin "1") (pinfunction "TXD_1") (pintype "output"))
    )
    (net (code "20") (name "GND") (class "Default")
      (node (ref "C1") (pin "-") (pinfunction "-_-") (pintype "passive"))
      (node (ref "C10") (pin "1") (pinfunction "P$1_1") (pintype "passive"))
      (node (ref "C11") (pin "2") (pinfunction "P$2_2") (pintype "passive"))
      (node (ref "C12") (pin "2") (pinfunction "P$2_2") (pintype "passive"))
      (node (ref "C13") (pin "1") (pinfunction "P$1_1") (pintype "passive"))
      (node (ref "C14") (pin "1") (pinfunction "P$1_1") (pintype "passive"))
      (node (ref "C15") (pin "1") (pinfunction "P$1_1") (pintype "passive"))
      (node (ref "C16") (pin "1") (pinfunction "P$1_1") (pintype "passive"))
      (node (ref "C17") (pin "1") (pinfunction "P$1_1") (pintype "passive"))
      (node (ref "C18") (pin "1") (pinfunction "P$1_1") (pintype "passive"))
      (node (ref "C19") (pin "1") (pinfunction "P$1_1") (pintype "passive"))
      (node (ref "C2") (pin "-") (pinfunction "-_-") (pintype "passive"))
      (node (ref "C20") (pin "1") (pinfunction "P$1_1") (pintype "passive"))
      (node (ref "C21") (pin "1") (pinfunction "P$1_1") (pintype "passive"))
      (node (ref "C22") (pin "1") (pinfunction "P$1_1") (pintype "passive"))
      (node (ref "C23") (pin "2") (pinfunction "P$2_2") (pintype "passive"))
      (node (ref "C24") (pin "2") (pinfunction "P$2_2") (pintype "passive"))
      (node (ref "C3") (pin "-") (pinfunction "-_-") (pintype "passive"))
      (node (ref "C4") (pin "1") (pinfunction "P$1_1") (pintype "passive"))
      (node (ref "C5") (pin "-") (pinfunction "-_-") (pintype "passive"))
      (node (ref "C6") (pin "1") (pinfunction "P$1_1") (pintype "passive"))
      (node (ref "C7") (pin "1") (pinfunction "P$1_1") (pintype "passive"))
      (node (ref "C8") (pin "1") (pinfunction "P$1_1") (pintype "passive"))
      (node (ref "C9") (pin "2") (pinfunction "P$2_2") (pintype "passive"))
      (node (ref "CON1") (pin "1") (pinfunction "3_1") (pintype "passive"))
      (node (ref "CON1") (pin "2") (pinfunction "2_2") (pintype "passive"))
      (node (ref "CON2") (pin "11") (pinfunction "CLKS_11") (pintype "bidirectional"))
      (node (ref "CON2") (pin "17") (pinfunction "GND_17") (pintype "bidirectional"))
      (node (ref "CON2") (pin "2") (pinfunction "DATA2S_2") (pintype "bidirectional"))
      (node (ref "CON2") (pin "5") (pinfunction "DATA1S_5") (pintype "bidirectional"))
      (node (ref "CON2") (pin "8") (pinfunction "DATA0S_8") (pintype "bidirectional"))
      (node (ref "CON2") (pin "GND@1") (pinfunction "GND_GND@1") (pintype "power_in"))
      (node (ref "CON2") (pin "GND@2") (pinfunction "GND_GND@2") (pintype "power_in"))
      (node (ref "CON2") (pin "GND@3") (pinfunction "GND_GND@3") (pintype "power_in"))
      (node (ref "CON2") (pin "GND@4") (pinfunction "GND_GND@4") (pintype "power_in"))
      (node (ref "CON3") (pin "1") (pinfunction "LED-K_1") (pintype "bidirectional"))
      (node (ref "CON3") (pin "29") (pinfunction "GND_29") (pintype "bidirectional"))
      (node (ref "CON3") (pin "3") (pinfunction "GND_3") (pintype "bidirectional"))
      (node (ref "CON3") (pin "36") (pinfunction "GND_36") (pintype "bidirectional"))
      (node (ref "CON3") (pin "GND@1") (pinfunction "GND_GND@1") (pintype "power_in"))
      (node (ref "CON3") (pin "GND@2") (pinfunction "GND_GND@2") (pintype "power_in"))
      (node (ref "CON4") (pin "5") (pinfunction "GND_5") (pintype "bidirectional"))
      (node (ref "CON4") (pin "GND@1") (pinfunction "GND_GND@1") (pintype "power_in"))
      (node (ref "CON4") (pin "GND@2") (pinfunction "GND_GND@2") (pintype "power_in"))
      (node (ref "CON4") (pin "GND@3") (pinfunction "GND_GND@3") (pintype "power_in"))
      (node (ref "CON4") (pin "GND@4") (pinfunction "GND_GND@4") (pintype "power_in"))
      (node (ref "CON5") (pin "6") (pinfunction "GND_6") (pintype "bidirectional"))
      (node (ref "CON5") (pin "GND@1") (pinfunction "GND_GND@1") (pintype "power_in"))
      (node (ref "CON5") (pin "GND@2") (pinfunction "GND_GND@2") (pintype "power_in"))
      (node (ref "CON6") (pin "12") (pinfunction "GND_12") (pintype "bidirectional"))
      (node (ref "CON6") (pin "15") (pinfunction "GND_15") (pintype "bidirectional"))
      (node (ref "CON6") (pin "18") (pinfunction "GND_18") (pintype "bidirectional"))
      (node (ref "CON6") (pin "21") (pinfunction "GND_21") (pintype "bidirectional"))
      (node (ref "CON6") (pin "26") (pinfunction "GND_26") (pintype "bidirectional"))
      (node (ref "CON6") (pin "3") (pinfunction "GND_3") (pintype "bidirectional"))
      (node (ref "CON6") (pin "4") (pinfunction "GND_4") (pintype "bidirectional"))
      (node (ref "CON6") (pin "6") (pinfunction "GND_6") (pintype "bidirectional"))
      (node (ref "CON6") (pin "9") (pinfunction "GND_9") (pintype "bidirectional"))
      (node (ref "CON6") (pin "GND@1") (pinfunction "GND_GND@1") (pintype "power_in"))
      (node (ref "CON6") (pin "GND@2") (pinfunction "GND_GND@2") (pintype "power_in"))
      (node (ref "CON6") (pin "GND@3") (pinfunction "GND_GND@3") (pintype "power_in"))
      (node (ref "CON6") (pin "GND@4") (pinfunction "GND_GND@4") (pintype "power_in"))
      (node (ref "IC1") (pin "2") (pinfunction "GND_2") (pintype "bidirectional"))
      (node (ref "IC1") (pin "6") (pinfunction "PGND_6") (pintype "bidirectional"))
      (node (ref "IC2") (pin "2") (pinfunction "GND_2") (pintype "bidirectional"))
      (node (ref "IC2") (pin "6") (pinfunction "PGND_6") (pintype "bidirectional"))
      (node (ref "IC4") (pin "1") (pinfunction "A0_1") (pintype "input"))
      (node (ref "IC4") (pin "2") (pinfunction "A1_2") (pintype "input"))
      (node (ref "IC4") (pin "3") (pinfunction "A2_3") (pintype "input"))
      (node (ref "IC4") (pin "4") (pinfunction "GND_4") (pintype "power_in"))
      (node (ref "IC5") (pin "1") (pinfunction "DFO_1") (pintype "bidirectional"))
      (node (ref "IC5") (pin "19") (pinfunction "OGND_19") (pintype "power_in"))
      (node (ref "IC5") (pin "28") (pinfunction "OGND_28") (pintype "power_in"))
      (node (ref "IC5") (pin "3") (pinfunction "ST_3") (pintype "bidirectional"))
      (node (ref "IC5") (pin "39") (pinfunction "DGND_39") (pintype "power_in"))
      (node (ref "IC5") (pin "45") (pinfunction "OGND_45") (pintype "power_in"))
      (node (ref "IC5") (pin "5") (pinfunction "DGND_5") (pintype "power_in"))
      (node (ref "IC5") (pin "58") (pinfunction "OGND_58") (pintype "power_in"))
      (node (ref "IC5") (pin "68") (pinfunction "DGND_68") (pintype "power_in"))
      (node (ref "IC5") (pin "7") (pinfunction "~{STAG}_7") (pintype "bidirectional"))
      (node (ref "IC5") (pin "76") (pinfunction "OGND_76") (pintype "power_in"))
      (node (ref "IC5") (pin "79") (pinfunction "AGND_79") (pintype "power_in"))
      (node (ref "IC5") (pin "83") (pinfunction "AGND_83") (pintype "power_in"))
      (node (ref "IC5") (pin "87") (pinfunction "AGND_87") (pintype "power_in"))
      (node (ref "IC5") (pin "89") (pinfunction "AGND_89") (pintype "power_in"))
      (node (ref "IC5") (pin "92") (pinfunction "AGND_92") (pintype "power_in"))
      (node (ref "IC5") (pin "98") (pinfunction "PGND_98") (pintype "power_in"))
      (node (ref "IC6") (pin "21") (pinfunction "GND_21") (pintype "power_in"))
      (node (ref "IC6") (pin "3") (pinfunction "GND_3") (pintype "power_in"))
      (node (ref "IC6") (pin "5") (pinfunction "GND_5") (pintype "power_in"))
      (node (ref "IC7") (pin "18") (pinfunction "GND_18") (pintype "power_in"))
      (node (ref "IC7") (pin "21") (pinfunction "GND_21") (pintype "power_in"))
      (node (ref "IC7") (pin "25") (pinfunction "GND_25") (pintype "power_in"))
      (node (ref "IC7") (pin "26") (pinfunction "TEST_26") (pintype "input"))
      (node (ref "IC7") (pin "7") (pinfunction "GND_7") (pintype "power_in"))
      (node (ref "IC8") (pin "13") (pinfunction "GND_13") (pintype "power_in"))
      (node (ref "IC8") (pin "21") (pinfunction "GND_21") (pintype "power_in"))
      (node (ref "IC8") (pin "25") (pinfunction "D23_25") (pintype "bidirectional"))
      (node (ref "IC8") (pin "29") (pinfunction "GND_29") (pintype "power_in"))
      (node (ref "IC8") (pin "33") (pinfunction "GND_33") (pintype "power_in"))
      (node (ref "IC8") (pin "35") (pinfunction "GND_35") (pintype "power_in"))
      (node (ref "IC8") (pin "36") (pinfunction "GND_36") (pintype "power_in"))
      (node (ref "IC8") (pin "43") (pinfunction "GND_43") (pintype "power_in"))
      (node (ref "IC8") (pin "49") (pinfunction "GND_49") (pintype "power_in"))
      (node (ref "IC8") (pin "5") (pinfunction "GND_5") (pintype "power_in"))
      (node (ref "IC8") (pin "53") (pinfunction "GND_53") (pintype "power_in"))
      (node (ref "JP1") (pin "1") (pinfunction "1_1") (pintype "passive"))
      (node (ref "JP2") (pin "1") (pinfunction "1_1") (pintype "passive"))
      (node (ref "JP3") (pin "1") (pinfunction "1_1") (pintype "passive"))
      (node (ref "JP5") (pin "1") (pinfunction "1_1") (pintype "passive"))
      (node (ref "JP7") (pin "1") (pinfunction "1_1") (pintype "passive"))
      (node (ref "JP8") (pin "1") (pinfunction "1_1") (pintype "passive"))
      (node (ref "R1") (pin "1") (pinfunction "P$1_1") (pintype "passive"))
      (node (ref "R14") (pin "2") (pinfunction "P$2_2") (pintype "passive"))
      (node (ref "R19") (pin "3") (pinfunction "A_3") (pintype "passive"))
      (node (ref "R24") (pin "1") (pinfunction "P$1_1") (pintype "passive"))
      (node (ref "R25") (pin "1") (pinfunction "P$1_1") (pintype "passive"))
      (node (ref "R26") (pin "1") (pinfunction "P$1_1") (pintype "passive"))
      (node (ref "R27") (pin "1") (pinfunction "P$1_1") (pintype "passive"))
    )
    (net (code "21") (name "HDMI_CLK_N") (class "Default")
      (node (ref "CON2") (pin "12") (pinfunction "CLK-_12") (pintype "bidirectional"))
      (node (ref "IC5") (pin "94") (pinfunction "RXC-_94") (pintype "bidirectional"))
    )
    (net (code "22") (name "HDMI_CLK_P") (class "Default")
      (node (ref "CON2") (pin "10") (pinfunction "CLK+_10") (pintype "bidirectional"))
      (node (ref "IC5") (pin "93") (pinfunction "RXC+_93") (pintype "bidirectional"))
    )
    (net (code "23") (name "HDMI_DAT0_N") (class "Default")
      (node (ref "CON2") (pin "9") (pinfunction "DATA0-_9") (pintype "bidirectional"))
      (node (ref "IC5") (pin "91") (pinfunction "RX0-_91") (pintype "bidirectional"))
    )
    (net (code "24") (name "HDMI_DAT0_P") (class "Default")
      (node (ref "CON2") (pin "7") (pinfunction "DATA0+_7") (pintype "bidirectional"))
      (node (ref "IC5") (pin "90") (pinfunction "RX0+_90") (pintype "bidirectional"))
    )
    (net (code "25") (name "HDMI_DAT1_N") (class "Default")
      (node (ref "CON2") (pin "6") (pinfunction "DATA1-_6") (pintype "bidirectional"))
      (node (ref "IC5") (pin "86") (pinfunction "RX1-_86") (pintype "bidirectional"))
    )
    (net (code "26") (name "HDMI_DAT1_P") (class "Default")
      (node (ref "CON2") (pin "4") (pinfunction "DATA1+_4") (pintype "bidirectional"))
      (node (ref "IC5") (pin "85") (pinfunction "RX1+_85") (pintype "bidirectional"))
    )
    (net (code "27") (name "HDMI_DAT2_N") (class "Default")
      (node (ref "CON2") (pin "3") (pinfunction "DATA2-_3") (pintype "bidirectional"))
      (node (ref "IC5") (pin "81") (pinfunction "RX2-_81") (pintype "bidirectional"))
    )
    (net (code "28") (name "HDMI_DAT2_P") (class "Default")
      (node (ref "CON2") (pin "1") (pinfunction "DATA2+_1") (pintype "bidirectional"))
      (node (ref "IC5") (pin "80") (pinfunction "RX2+_80") (pintype "bidirectional"))
    )
    (net (code "29") (name "HDMI_OCK_INV") (class "Default")
      (node (ref "IC5") (pin "100") (pinfunction "OCK_INV_100") (pintype "bidirectional"))
      (node (ref "JP1") (pin "2") (pinfunction "2_2") (pintype "passive"))
      (node (ref "R6") (pin "1") (pinfunction "P$1_1") (pintype "passive"))
    )
    (net (code "30") (name "HDMI_PIXS") (class "Default")
      (node (ref "IC5") (pin "4") (pinfunction "PIXS_4") (pintype "bidirectional"))
      (node (ref "JP2") (pin "2") (pinfunction "2_2") (pintype "passive"))
      (node (ref "R5") (pin "1") (pinfunction "P$1_1") (pintype "passive"))
    )
    (net (code "31") (name "LVDS_0_N") (class "Default")
      (node (ref "CON6") (pin "7") (pinfunction "RA-_7") (pintype "bidirectional"))
      (node (ref "IC8") (pin "48") (pinfunction "Y0M_48") (pintype "bidirectional"))
    )
    (net (code "32") (name "LVDS_0_P") (class "Default")
      (node (ref "CON6") (pin "8") (pinfunction "RA+_8") (pintype "bidirectional"))
      (node (ref "IC8") (pin "47") (pinfunction "Y0P_47") (pintype "bidirectional"))
    )
    (net (code "33") (name "LVDS_1_N") (class "Default")
      (node (ref "CON6") (pin "10") (pinfunction "RB-_10") (pintype "bidirectional"))
      (node (ref "IC8") (pin "46") (pinfunction "Y1M_46") (pintype "bidirectional"))
    )
    (net (code "34") (name "LVDS_1_P") (class "Default")
      (node (ref "CON6") (pin "11") (pinfunction "RB+_11") (pintype "bidirectional"))
      (node (ref "IC8") (pin "45") (pinfunction "Y1P_45") (pintype "bidirectional"))
    )
    (net (code "35") (name "LVDS_2_N") (class "Default")
      (node (ref "CON6") (pin "13") (pinfunction "RC-_13") (pintype "bidirectional"))
      (node (ref "IC8") (pin "42") (pinfunction "Y2M_42") (pintype "bidirectional"))
    )
    (net (code "36") (name "LVDS_2_P") (class "Default")
      (node (ref "CON6") (pin "14") (pinfunction "RC+_14") (pintype "bidirectional"))
      (node (ref "IC8") (pin "41") (pinfunction "Y2P_41") (pintype "bidirectional"))
    )
    (net (code "37") (name "LVDS_3_N") (class "Default")
      (node (ref "CON6") (pin "19") (pinfunction "RDM-_19") (pintype "bidirectional"))
      (node (ref "IC8") (pin "38") (pinfunction "Y3M_38") (pintype "bidirectional"))
    )
    (net (code "38") (name "LVDS_3_P") (class "Default")
      (node (ref "CON6") (pin "20") (pinfunction "RDM+_20") (pintype "bidirectional"))
      (node (ref "IC8") (pin "37") (pinfunction "Y3P_37") (pintype "bidirectional"))
    )
    (net (code "39") (name "LVDS_CLK_N") (class "Default")
      (node (ref "CON6") (pin "16") (pinfunction "RCLK-_16") (pintype "bidirectional"))
      (node (ref "IC8") (pin "40") (pinfunction "CLKOUTM_40") (pintype "bidirectional"))
    )
    (net (code "40") (name "LVDS_CLK_P") (class "Default")
      (node (ref "CON6") (pin "17") (pinfunction "RCLK+_17") (pintype "bidirectional"))
      (node (ref "IC8") (pin "39") (pinfunction "CLKOUTP_39") (pintype "bidirectional"))
    )
    (net (code "41") (name "LVDS_LED_EN") (class "Default")
      (node (ref "CON6") (pin "25") (pinfunction "LED_EN_25") (pintype "bidirectional"))
      (node (ref "JP8") (pin "2") (pinfunction "2_2") (pintype "passive"))
      (node (ref "R4") (pin "1") (pinfunction "P$1_1") (pintype "passive"))
    )
    (net (code "42") (name "LVDS_PWM") (class "Default")
      (node (ref "CON6") (pin "24") (pinfunction "PWM_24") (pintype "bidirectional"))
      (node (ref "JP6") (pin "3") (pinfunction "3_3") (pintype "passive"))
    )
    (net (code "43") (name "LVDS_REVSCAN") (class "Default")
      (node (ref "CON6") (pin "5") (pinfunction "SHLI_5") (pintype "bidirectional"))
      (node (ref "JP7") (pin "2") (pinfunction "2_2") (pintype "passive"))
      (node (ref "R18") (pin "1") (pinfunction "P$1_1") (pintype "passive"))
    )
    (net (code "44") (name "Net-(C7-P$2)") (class "Default")
      (node (ref "C7") (pin "2") (pinfunction "P$2_2") (pintype "passive"))
      (node (ref "IC6") (pin "7") (pinfunction "PB6(PCINT6/XTAL1/TOSC1)_7") (pintype "bidirectional"))
      (node (ref "Q1") (pin "2") (pinfunction "2_2") (pintype "passive"))
    )
    (net (code "45") (name "Net-(C8-P$2)") (class "Default")
      (node (ref "C8") (pin "2") (pinfunction "P$2_2") (pintype "passive"))
      (node (ref "IC6") (pin "8") (pinfunction "PB7(PCINT7/XTAL2/TOSC2)_8") (pintype "bidirectional"))
      (node (ref "Q1") (pin "1") (pinfunction "1_1") (pintype "passive"))
    )
    (net (code "46") (name "Net-(C11-P$1)") (class "Default")
      (node (ref "C11") (pin "1") (pinfunction "P$1_1") (pintype "passive"))
      (node (ref "IC7") (pin "17") (pinfunction "3V3OUT_17") (pintype "output"))
    )
    (net (code "47") (name "Net-(CON1-1)") (class "Default")
      (node (ref "CON1") (pin "3") (pinfunction "1_3") (pintype "passive"))
      (node (ref "T1") (pin "2") (pinfunction "D_2") (pintype "passive"))
    )
    (net (code "48") (name "Net-(CON2-DETECT)") (class "Default")
      (node (ref "CON2") (pin "19") (pinfunction "DETECT_19") (pintype "bidirectional"))
      (node (ref "R7") (pin "1") (pinfunction "P$1_1") (pintype "passive"))
    )
    (net (code "49") (name "Net-(CON3-LED-A)") (class "Default")
      (node (ref "CON3") (pin "2") (pinfunction "LED-A_2") (pintype "bidirectional"))
      (node (ref "T2") (pin "2") (pinfunction "S_2") (pintype "passive"))
    )
    (net (code "50") (name "Net-(IC3-GND)") (class "Default")
      (node (ref "IC3") (pin "1") (pinfunction "GND_1") (pintype "input"))
      (node (ref "R13") (pin "1") (pinfunction "P$1_1") (pintype "passive"))
      (node (ref "R14") (pin "1") (pinfunction "P$1_1") (pintype "passive"))
    )
    (net (code "51") (name "Net-(IC5-DE)") (class "Default")
      (node (ref "IC5") (pin "46") (pinfunction "DE_46") (pintype "bidirectional"))
      (node (ref "R2") (pin "3M") (pinfunction "3M_3M") (pintype "bidirectional"))
    )
    (net (code "52") (name "Net-(IC5-HSYNC)") (class "Default")
      (node (ref "IC5") (pin "48") (pinfunction "HSYNC_48") (pintype "bidirectional"))
      (node (ref "R2") (pin "1M") (pinfunction "1M_1M") (pintype "bidirectional"))
    )
    (net (code "53") (name "Net-(IC5-ODCK)") (class "Default")
      (node (ref "IC5") (pin "44") (pinfunction "ODCK_44") (pintype "bidirectional"))
      (node (ref "R2") (pin "4M") (pinfunction "4M_4M") (pintype "bidirectional"))
    )
    (net (code "54") (name "Net-(IC5-QE0)") (class "Default")
      (node (ref "IC5") (pin "10") (pinfunction "QE0_10") (pintype "bidirectional"))
      (node (ref "R3") (pin "4M") (pinfunction "4M_4M") (pintype "bidirectional"))
    )
    (net (code "55") (name "Net-(IC5-QE1)") (class "Default")
      (node (ref "IC5") (pin "11") (pinfunction "QE1_11") (pintype "bidirectional"))
      (node (ref "R3") (pin "3M") (pinfunction "3M_3M") (pintype "bidirectional"))
    )
    (net (code "56") (name "Net-(IC5-QE2)") (class "Default")
      (node (ref "IC5") (pin "12") (pinfunction "QE2_12") (pintype "bidirectional"))
      (node (ref "R3") (pin "2M") (pinfunction "2M_2M") (pintype "bidirectional"))
    )
    (net (code "57") (name "Net-(IC5-QE3)") (class "Default")
      (node (ref "IC5") (pin "13") (pinfunction "QE3_13") (pintype "bidirectional"))
      (node (ref "R3") (pin "1M") (pinfunction "1M_1M") (pintype "bidirectional"))
    )
    (net (code "58") (name "Net-(IC5-QE4)") (class "Default")
      (node (ref "IC5") (pin "14") (pinfunction "QE4_14") (pintype "bidirectional"))
      (node (ref "R8") (pin "4M") (pinfunction "4M_4M") (pintype "bidirectional"))
    )
    (net (code "59") (name "Net-(IC5-QE5)") (class "Default")
      (node (ref "IC5") (pin "15") (pinfunction "QE5_15") (pintype "bidirectional"))
      (node (ref "R8") (pin "3M") (pinfunction "3M_3M") (pintype "bidirectional"))
    )
    (net (code "60") (name "Net-(IC5-QE6)") (class "Default")
      (node (ref "IC5") (pin "16") (pinfunction "QE6_16") (pintype "bidirectional"))
      (node (ref "R8") (pin "2M") (pinfunction "2M_2M") (pintype "bidirectional"))
    )
    (net (code "61") (name "Net-(IC5-QE7)") (class "Default")
      (node (ref "IC5") (pin "17") (pinfunction "QE7_17") (pintype "bidirectional"))
      (node (ref "R8") (pin "1M") (pinfunction "1M_1M") (pintype "bidirectional"))
    )
    (net (code "62") (name "Net-(IC5-QE8)") (class "Default")
      (node (ref "IC5") (pin "20") (pinfunction "QE8_20") (pintype "bidirectional"))
      (node (ref "R9") (pin "4M") (pinfunction "4M_4M") (pintype "bidirectional"))
    )
    (net (code "63") (name "Net-(IC5-QE9)") (class "Default")
      (node (ref "IC5") (pin "21") (pinfunction "QE9_21") (pintype "bidirectional"))
      (node (ref "R9") (pin "3M") (pinfunction "3M_3M") (pintype "bidirectional"))
    )
    (net (code "64") (name "Net-(IC5-QE10)") (class "Default")
      (node (ref "IC5") (pin "22") (pinfunction "QE10_22") (pintype "bidirectional"))
      (node (ref "R9") (pin "2M") (pinfunction "2M_2M") (pintype "bidirectional"))
    )
    (net (code "65") (name "Net-(IC5-QE11)") (class "Default")
      (node (ref "IC5") (pin "23") (pinfunction "QE11_23") (pintype "bidirectional"))
      (node (ref "R9") (pin "1M") (pinfunction "1M_1M") (pintype "bidirectional"))
    )
    (net (code "66") (name "Net-(IC5-QE12)") (class "Default")
      (node (ref "IC5") (pin "24") (pinfunction "QE12_24") (pintype "bidirectional"))
      (node (ref "R10") (pin "4M") (pinfunction "4M_4M") (pintype "bidirectional"))
    )
    (net (code "67") (name "Net-(IC5-QE13)") (class "Default")
      (node (ref "IC5") (pin "25") (pinfunction "QE13_25") (pintype "bidirectional"))
      (node (ref "R10") (pin "3M") (pinfunction "3M_3M") (pintype "bidirectional"))
    )
    (net (code "68") (name "Net-(IC5-QE14)") (class "Default")
      (node (ref "IC5") (pin "26") (pinfunction "QE14_26") (pintype "bidirectional"))
      (node (ref "R10") (pin "2M") (pinfunction "2M_2M") (pintype "bidirectional"))
    )
    (net (code "69") (name "Net-(IC5-QE15)") (class "Default")
      (node (ref "IC5") (pin "27") (pinfunction "QE15_27") (pintype "bidirectional"))
      (node (ref "R10") (pin "1M") (pinfunction "1M_1M") (pintype "bidirectional"))
    )
    (net (code "70") (name "Net-(IC5-QE16)") (class "Default")
      (node (ref "IC5") (pin "30") (pinfunction "QE16_30") (pintype "bidirectional"))
      (node (ref "R11") (pin "4M") (pinfunction "4M_4M") (pintype "bidirectional"))
    )
    (net (code "71") (name "Net-(IC5-QE17)") (class "Default")
      (node (ref "IC5") (pin "31") (pinfunction "QE17_31") (pintype "bidirectional"))
      (node (ref "R11") (pin "3M") (pinfunction "3M_3M") (pintype "bidirectional"))
    )
    (net (code "72") (name "Net-(IC5-QE18)") (class "Default")
      (node (ref "IC5") (pin "32") (pinfunction "QE18_32") (pintype "bidirectional"))
      (node (ref "R11") (pin "2M") (pinfunction "2M_2M") (pintype "bidirectional"))
    )
    (net (code "73") (name "Net-(IC5-QE19)") (class "Default")
      (node (ref "IC5") (pin "33") (pinfunction "QE19_33") (pintype "bidirectional"))
      (node (ref "R11") (pin "1M") (pinfunction "1M_1M") (pintype "bidirectional"))
    )
    (net (code "74") (name "Net-(IC5-QE20)") (class "Default")
      (node (ref "IC5") (pin "34") (pinfunction "QE20_34") (pintype "bidirectional"))
      (node (ref "R12") (pin "4M") (pinfunction "4M_4M") (pintype "bidirectional"))
    )
    (net (code "75") (name "Net-(IC5-QE21)") (class "Default")
      (node (ref "IC5") (pin "35") (pinfunction "QE21_35") (pintype "bidirectional"))
      (node (ref "R12") (pin "3M") (pinfunction "3M_3M") (pintype "bidirectional"))
    )
    (net (code "76") (name "Net-(IC5-QE22)") (class "Default")
      (node (ref "IC5") (pin "36") (pinfunction "QE22_36") (pintype "bidirectional"))
      (node (ref "R12") (pin "2M") (pinfunction "2M_2M") (pintype "bidirectional"))
    )
    (net (code "77") (name "Net-(IC5-QE23)") (class "Default")
      (node (ref "IC5") (pin "37") (pinfunction "QE23_37") (pintype "bidirectional"))
      (node (ref "R12") (pin "1M") (pinfunction "1M_1M") (pintype "bidirectional"))
    )
    (net (code "78") (name "Net-(IC5-VSYNC)") (class "Default")
      (node (ref "IC5") (pin "47") (pinfunction "VSYNC_47") (pintype "bidirectional"))
      (node (ref "R2") (pin "2M") (pinfunction "2M_2M") (pintype "bidirectional"))
    )
    (net (code "79") (name "Net-(IC7-USBDM)") (class "Default")
      (node (ref "IC7") (pin "16") (pinfunction "USBDM_16") (pintype "bidirectional"))
      (node (ref "R23") (pin "2") (pinfunction "P$2_2") (pintype "passive"))
    )
    (net (code "80") (name "Net-(IC7-USBDP)") (class "Default")
      (node (ref "IC7") (pin "15") (pinfunction "USBDP_15") (pintype "bidirectional"))
      (node (ref "R22") (pin "2") (pinfunction "P$2_2") (pintype "passive"))
    )
    (net (code "81") (name "Net-(R1-P$2)") (class "Default")
      (node (ref "D1") (pin "A") (pinfunction "A_A") (pintype "passive"))
      (node (ref "R1") (pin "2") (pinfunction "P$2_2") (pintype "passive"))
      (node (ref "T1") (pin "1") (pinfunction "G_1") (pintype "passive"))
    )
    (net (code "82") (name "Net-(R20-P$1)") (class "Default")
      (node (ref "R20") (pin "1") (pinfunction "P$1_1") (pintype "passive"))
      (node (ref "R21") (pin "1") (pinfunction "P$1_1") (pintype "passive"))
      (node (ref "T2") (pin "3") (pinfunction "D_3") (pintype "passive"))
    )
    (net (code "83") (name "Net-(R24-P$2)") (class "Default")
      (node (ref "LED1") (pin "A") (pinfunction "A_A") (pintype "passive"))
      (node (ref "R24") (pin "2") (pinfunction "P$2_2") (pintype "passive"))
    )
    (net (code "84") (name "Net-(R25-P$2)") (class "Default")
      (node (ref "LED2") (pin "A") (pinfunction "A_A") (pintype "passive"))
      (node (ref "R25") (pin "2") (pinfunction "P$2_2") (pintype "passive"))
    )
    (net (code "85") (name "Net-(R26-P$2)") (class "Default")
      (node (ref "LED3") (pin "A") (pinfunction "A_A") (pintype "passive"))
      (node (ref "R26") (pin "2") (pinfunction "P$2_2") (pintype "passive"))
    )
    (net (code "86") (name "Net-(R27-P$2)") (class "Default")
      (node (ref "LED4") (pin "A") (pinfunction "A_A") (pintype "passive"))
      (node (ref "R27") (pin "2") (pinfunction "P$2_2") (pintype "passive"))
    )
    (net (code "87") (name "RGB_DE") (class "Default")
      (node (ref "CON3") (pin "34") (pinfunction "DEN_34") (pintype "bidirectional"))
      (node (ref "IC8") (pin "30") (pinfunction "D26_30") (pintype "bidirectional"))
      (node (ref "R2") (pin "3P") (pinfunction "3P_3P") (pintype "bidirectional"))
    )
    (net (code "88") (name "RGB_DISP") (class "Default")
      (node (ref "CON3") (pin "31") (pinfunction "DISP_31") (pintype "bidirectional"))
      (node (ref "JP3") (pin "2") (pinfunction "2_2") (pintype "passive"))
      (node (ref "R15") (pin "1") (pinfunction "P$1_1") (pintype "passive"))
    )
    (net (code "89") (name "RGB_EVEN_B0") (class "Default")
      (node (ref "CON3") (pin "21") (pinfunction "B0_21") (pintype "bidirectional"))
      (node (ref "IC8") (pin "15") (pinfunction "D15_15") (pintype "bidirectional"))
      (node (ref "R3") (pin "4P") (pinfunction "4P_4P") (pintype "bidirectional"))
    )
    (net (code "90") (name "RGB_EVEN_B1") (class "Default")
      (node (ref "CON3") (pin "22") (pinfunction "B1_22") (pintype "bidirectional"))
      (node (ref "IC8") (pin "19") (pinfunction "D18_19") (pintype "bidirectional"))
      (node (ref "R3") (pin "3P") (pinfunction "3P_3P") (pintype "bidirectional"))
    )
    (net (code "91") (name "RGB_EVEN_B2") (class "Default")
      (node (ref "CON3") (pin "23") (pinfunction "B2_23") (pintype "bidirectional"))
      (node (ref "IC8") (pin "20") (pinfunction "D19_20") (pintype "bidirectional"))
      (node (ref "R3") (pin "2P") (pinfunction "2P_2P") (pintype "bidirectional"))
    )
    (net (code "92") (name "RGB_EVEN_B3") (class "Default")
      (node (ref "CON3") (pin "24") (pinfunction "B3_24") (pintype "bidirectional"))
      (node (ref "IC8") (pin "22") (pinfunction "D20_22") (pintype "bidirectional"))
      (node (ref "R3") (pin "1P") (pinfunction "1P_1P") (pintype "bidirectional"))
    )
    (net (code "93") (name "RGB_EVEN_B4") (class "Default")
      (node (ref "CON3") (pin "25") (pinfunction "B4_25") (pintype "bidirectional"))
      (node (ref "IC8") (pin "23") (pinfunction "D21_23") (pintype "bidirectional"))
      (node (ref "R8") (pin "4P") (pinfunction "4P_4P") (pintype "bidirectional"))
    )
    (net (code "94") (name "RGB_EVEN_B5") (class "Default")
      (node (ref "CON3") (pin "26") (pinfunction "B5_26") (pintype "bidirectional"))
      (node (ref "IC8") (pin "24") (pinfunction "D22_24") (pintype "bidirectional"))
      (node (ref "R8") (pin "3P") (pinfunction "3P_3P") (pintype "bidirectional"))
    )
    (net (code "95") (name "RGB_EVEN_B6") (class "Default")
      (node (ref "CON3") (pin "27") (pinfunction "B6_27") (pintype "bidirectional"))
      (node (ref "IC8") (pin "16") (pinfunction "D16_16") (pintype "bidirectional"))
      (node (ref "R8") (pin "2P") (pinfunction "2P_2P") (pintype "bidirectional"))
    )
    (net (code "96") (name "RGB_EVEN_B7") (class "Default")
      (node (ref "CON3") (pin "28") (pinfunction "B7_28") (pintype "bidirectional"))
      (node (ref "IC8") (pin "18") (pinfunction "D17_18") (pintype "bidirectional"))
      (node (ref "R8") (pin "1P") (pinfunction "1P_1P") (pintype "bidirectional"))
    )
    (net (code "97") (name "RGB_EVEN_G0") (class "Default")
      (node (ref "CON3") (pin "13") (pinfunction "G0_13") (pintype "bidirectional"))
      (node (ref "IC8") (pin "4") (pinfunction "D7_4") (pintype "bidirectional"))
      (node (ref "R9") (pin "4P") (pinfunction "4P_4P") (pintype "bidirectional"))
    )
    (net (code "98") (name "RGB_EVEN_G1") (class "Default")
      (node (ref "CON3") (pin "14") (pinfunction "G1_14") (pintype "bidirectional"))
      (node (ref "IC8") (pin "6") (pinfunction "D8_6") (pintype "bidirectional"))
      (node (ref "R9") (pin "3P") (pinfunction "3P_3P") (pintype "bidirectional"))
    )
    (net (code "99") (name "RGB_EVEN_G2") (class "Default")
      (node (ref "CON3") (pin "15") (pinfunction "G2_15") (pintype "bidirectional"))
      (node (ref "IC8") (pin "7") (pinfunction "D9_7") (pintype "bidirectional"))
      (node (ref "R9") (pin "2P") (pinfunction "2P_2P") (pintype "bidirectional"))
    )
    (net (code "100") (name "RGB_EVEN_G3") (class "Default")
      (node (ref "CON3") (pin "16") (pinfunction "G3_16") (pintype "bidirectional"))
      (node (ref "IC8") (pin "11") (pinfunction "D12_11") (pintype "bidirectional"))
      (node (ref "R9") (pin "1P") (pinfunction "1P_1P") (pintype "bidirectional"))
    )
    (net (code "101") (name "RGB_EVEN_G4") (class "Default")
      (node (ref "CON3") (pin "17") (pinfunction "G4_17") (pintype "bidirectional"))
      (node (ref "IC8") (pin "12") (pinfunction "D13_12") (pintype "bidirectional"))
      (node (ref "R10") (pin "4P") (pinfunction "4P_4P") (pintype "bidirectional"))
    )
    (net (code "102") (name "RGB_EVEN_G5") (class "Default")
      (node (ref "CON3") (pin "18") (pinfunction "G5_18") (pintype "bidirectional"))
      (node (ref "IC8") (pin "14") (pinfunction "D14_14") (pintype "bidirectional"))
      (node (ref "R10") (pin "3P") (pinfunction "3P_3P") (pintype "bidirectional"))
    )
    (net (code "103") (name "RGB_EVEN_G6") (class "Default")
      (node (ref "CON3") (pin "19") (pinfunction "G6_19") (pintype "bidirectional"))
      (node (ref "IC8") (pin "8") (pinfunction "D10_8") (pintype "bidirectional"))
      (node (ref "R10") (pin "2P") (pinfunction "2P_2P") (pintype "bidirectional"))
    )
    (net (code "104") (name "RGB_EVEN_G7") (class "Default")
      (node (ref "CON3") (pin "20") (pinfunction "G7_20") (pintype "bidirectional"))
      (node (ref "IC8") (pin "10") (pinfunction "D11_10") (pintype "bidirectional"))
      (node (ref "R10") (pin "1P") (pinfunction "1P_1P") (pintype "bidirectional"))
    )
    (net (code "105") (name "RGB_EVEN_R0") (class "Default")
      (node (ref "CON3") (pin "5") (pinfunction "R0_5") (pintype "bidirectional"))
      (node (ref "IC8") (pin "51") (pinfunction "D0_51") (pintype "bidirectional"))
      (node (ref "R11") (pin "4P") (pinfunction "4P_4P") (pintype "bidirectional"))
    )
    (net (code "106") (name "RGB_EVEN_R1") (class "Default")
      (node (ref "CON3") (pin "6") (pinfunction "R1_6") (pintype "bidirectional"))
      (node (ref "IC8") (pin "52") (pinfunction "D1_52") (pintype "bidirectional"))
      (node (ref "R11") (pin "3P") (pinfunction "3P_3P") (pintype "bidirectional"))
    )
    (net (code "107") (name "RGB_EVEN_R2") (class "Default")
      (node (ref "CON3") (pin "7") (pinfunction "R2_7") (pintype "bidirectional"))
      (node (ref "IC8") (pin "54") (pinfunction "D2_54") (pintype "bidirectional"))
      (node (ref "R11") (pin "2P") (pinfunction "2P_2P") (pintype "bidirectional"))
    )
    (net (code "108") (name "RGB_EVEN_R3") (class "Default")
      (node (ref "CON3") (pin "8") (pinfunction "R3_8") (pintype "bidirectional"))
      (node (ref "IC8") (pin "55") (pinfunction "D3_55") (pintype "bidirectional"))
      (node (ref "R11") (pin "1P") (pinfunction "1P_1P") (pintype "bidirectional"))
    )
    (net (code "109") (name "RGB_EVEN_R4") (class "Default")
      (node (ref "CON3") (pin "9") (pinfunction "R4_9") (pintype "bidirectional"))
      (node (ref "IC8") (pin "56") (pinfunction "D4_56") (pintype "bidirectional"))
      (node (ref "R12") (pin "4P") (pinfunction "4P_4P") (pintype "bidirectional"))
    )
    (net (code "110") (name "RGB_EVEN_R5") (class "Default")
      (node (ref "CON3") (pin "10") (pinfunction "R5_10") (pintype "bidirectional"))
      (node (ref "IC8") (pin "3") (pinfunction "D6_3") (pintype "bidirectional"))
      (node (ref "R12") (pin "3P") (pinfunction "3P_3P") (pintype "bidirectional"))
    )
    (net (code "111") (name "RGB_EVEN_R6") (class "Default")
      (node (ref "CON3") (pin "11") (pinfunction "R6_11") (pintype "bidirectional"))
      (node (ref "IC8") (pin "50") (pinfunction "D27_50") (pintype "bidirectional"))
      (node (ref "R12") (pin "2P") (pinfunction "2P_2P") (pintype "bidirectional"))
    )
    (net (code "112") (name "RGB_EVEN_R7") (class "Default")
      (node (ref "CON3") (pin "12") (pinfunction "R7_12") (pintype "bidirectional"))
      (node (ref "IC8") (pin "2") (pinfunction "D5_2") (pintype "bidirectional"))
      (node (ref "R12") (pin "1P") (pinfunction "1P_1P") (pintype "bidirectional"))
    )
    (net (code "113") (name "RGB_HSYNC") (class "Default")
      (node (ref "CON3") (pin "32") (pinfunction "HSYNC_32") (pintype "bidirectional"))
      (node (ref "IC8") (pin "27") (pinfunction "D24_27") (pintype "bidirectional"))
      (node (ref "R2") (pin "2P") (pinfunction "2P_2P") (pintype "bidirectional"))
    )
    (net (code "114") (name "RGB_ODCK") (class "Default")
      (node (ref "CON3") (pin "30") (pinfunction "CLK_30") (pintype "bidirectional"))
      (node (ref "R2") (pin "4P") (pinfunction "4P_4P") (pintype "bidirectional"))
    )
    (net (code "115") (name "RGB_PWM") (class "Default")
      (node (ref "JP4") (pin "3") (pinfunction "3_3") (pintype "passive"))
      (node (ref "JP6") (pin "1") (pinfunction "1_1") (pintype "passive"))
    )
    (net (code "116") (name "RGB_PWM_EN") (class "Default")
      (node (ref "JP4") (pin "2") (pinfunction "2_2") (pintype "passive"))
      (node (ref "T2") (pin "1") (pinfunction "G_1") (pintype "passive"))
    )
    (net (code "117") (name "RGB_VSYNC") (class "Default")
      (node (ref "CON3") (pin "33") (pinfunction "VSYNC_33") (pintype "bidirectional"))
      (node (ref "IC8") (pin "28") (pinfunction "D25_28") (pintype "bidirectional"))
      (node (ref "R2") (pin "1P") (pinfunction "1P_1P") (pintype "bidirectional"))
    )
    (net (code "118") (name "USB_D+") (class "Default")
      (node (ref "CON4") (pin "3") (pinfunction "D+_3") (pintype "bidirectional"))
      (node (ref "R23") (pin "1") (pinfunction "P$1_1") (pintype "passive"))
    )
    (net (code "119") (name "USB_D-") (class "Default")
      (node (ref "CON4") (pin "2") (pinfunction "D-_2") (pintype "bidirectional"))
      (node (ref "R22") (pin "1") (pinfunction "P$1_1") (pintype "passive"))
    )
    (net (code "120") (name "unconnected-(CON2-CEC-Pad13)") (class "Default")
      (node (ref "CON2") (pin "13") (pinfunction "CEC_13") (pintype "bidirectional"))
    )
    (net (code "121") (name "unconnected-(CON2-NC-Pad14)") (class "Default")
      (node (ref "CON2") (pin "14") (pinfunction "NC_14") (pintype "bidirectional"))
    )
    (net (code "122") (name "unconnected-(CON3-NC-Pad35)") (class "Default")
      (node (ref "CON3") (pin "35") (pinfunction "NC_35") (pintype "bidirectional"))
    )
    (net (code "123") (name "unconnected-(CON3-XL-Pad39)") (class "Default")
      (node (ref "CON3") (pin "39") (pinfunction "XL_39") (pintype "bidirectional"))
    )
    (net (code "124") (name "unconnected-(CON3-XR-Pad37)") (class "Default")
      (node (ref "CON3") (pin "37") (pinfunction "XR_37") (pintype "bidirectional"))
    )
    (net (code "125") (name "unconnected-(CON3-YD-Pad38)") (class "Default")
      (node (ref "CON3") (pin "38") (pinfunction "YD_38") (pintype "bidirectional"))
    )
    (net (code "126") (name "unconnected-(CON3-YU-Pad40)") (class "Default")
      (node (ref "CON3") (pin "40") (pinfunction "YU_40") (pintype "bidirectional"))
    )
    (net (code "127") (name "unconnected-(CON4-ID-Pad4)") (class "Default")
      (node (ref "CON4") (pin "4") (pinfunction "ID_4") (pintype "bidirectional"))
    )
    (net (code "128") (name "unconnected-(CON6-NC-Pad27)") (class "Default")
      (node (ref "CON6") (pin "27") (pinfunction "NC_27") (pintype "bidirectional"))
    )
    (net (code "129") (name "unconnected-(CON6-TP-Pad22)") (class "Default")
      (node (ref "CON6") (pin "22") (pinfunction "TP_22") (pintype "bidirectional"))
    )
    (net (code "130") (name "unconnected-(CON6-TP-Pad23)") (class "Default")
      (node (ref "CON6") (pin "23") (pinfunction "TP_23") (pintype "bidirectional"))
    )
    (net (code "131") (name "unconnected-(IC1-EN-Pad5)") (class "Default")
      (node (ref "IC1") (pin "5") (pinfunction "EN_5") (pintype "bidirectional"))
    )
    (net (code "132") (name "unconnected-(IC1-PG-Pad4)") (class "Default")
      (node (ref "IC1") (pin "4") (pinfunction "PG_4") (pintype "bidirectional"))
    )
    (net (code "133") (name "unconnected-(IC2-EN-Pad5)") (class "Default")
      (node (ref "IC2") (pin "5") (pinfunction "EN_5") (pintype "bidirectional"))
    )
    (net (code "134") (name "unconnected-(IC2-PG-Pad4)") (class "Default")
      (node (ref "IC2") (pin "4") (pinfunction "PG_4") (pintype "bidirectional"))
    )
    (net (code "135") (name "unconnected-(IC5-CTL1-Pad40)") (class "Default")
      (node (ref "IC5") (pin "40") (pinfunction "CTL1_40") (pintype "bidirectional"))
    )
    (net (code "136") (name "unconnected-(IC5-CTL2-Pad41)") (class "Default")
      (node (ref "IC5") (pin "41") (pinfunction "CTL2_41") (pintype "bidirectional"))
    )
    (net (code "137") (name "unconnected-(IC5-CTL3-Pad42)") (class "Default")
      (node (ref "IC5") (pin "42") (pinfunction "CTL3_42") (pintype "bidirectional"))
    )
    (net (code "138") (name "unconnected-(IC5-EXT_RES-Pad96)") (class "Default")
      (node (ref "IC5") (pin "96") (pinfunction "EXT_RES_96") (pintype "bidirectional"))
    )
    (net (code "139") (name "unconnected-(IC5-QO0-Pad49)") (class "Default")
      (node (ref "IC5") (pin "49") (pinfunction "QO0_49") (pintype "bidirectional"))
    )
    (net (code "140") (name "unconnected-(IC5-QO1-Pad50)") (class "Default")
      (node (ref "IC5") (pin "50") (pinfunction "QO1_50") (pintype "bidirectional"))
    )
    (net (code "141") (name "unconnected-(IC5-QO2-Pad51)") (class "Default")
      (node (ref "IC5") (pin "51") (pinfunction "QO2_51") (pintype "bidirectional"))
    )
    (net (code "142") (name "unconnected-(IC5-QO3-Pad52)") (class "Default")
      (node (ref "IC5") (pin "52") (pinfunction "QO3_52") (pintype "bidirectional"))
    )
    (net (code "143") (name "unconnected-(IC5-QO4-Pad53)") (class "Default")
      (node (ref "IC5") (pin "53") (pinfunction "QO4_53") (pintype "bidirectional"))
    )
    (net (code "144") (name "unconnected-(IC5-QO5-Pad54)") (class "Default")
      (node (ref "IC5") (pin "54") (pinfunction "QO5_54") (pintype "bidirectional"))
    )
    (net (code "145") (name "unconnected-(IC5-QO6-Pad55)") (class "Default")
      (node (ref "IC5") (pin "55") (pinfunction "QO6_55") (pintype "bidirectional"))
    )
    (net (code "146") (name "unconnected-(IC5-QO7-Pad56)") (class "Default")
      (node (ref "IC5") (pin "56") (pinfunction "QO7_56") (pintype "bidirectional"))
    )
    (net (code "147") (name "unconnected-(IC5-QO8-Pad59)") (class "Default")
      (node (ref "IC5") (pin "59") (pinfunction "QO8_59") (pintype "bidirectional"))
    )
    (net (code "148") (name "unconnected-(IC5-QO9-Pad60)") (class "Default")
      (node (ref "IC5") (pin "60") (pinfunction "QO9_60") (pintype "bidirectional"))
    )
    (net (code "149") (name "unconnected-(IC5-QO10-Pad61)") (class "Default")
      (node (ref "IC5") (pin "61") (pinfunction "QO10_61") (pintype "bidirectional"))
    )
    (net (code "150") (name "unconnected-(IC5-QO11-Pad62)") (class "Default")
      (node (ref "IC5") (pin "62") (pinfunction "QO11_62") (pintype "bidirectional"))
    )
    (net (code "151") (name "unconnected-(IC5-QO12-Pad63)") (class "Default")
      (node (ref "IC5") (pin "63") (pinfunction "QO12_63") (pintype "bidirectional"))
    )
    (net (code "152") (name "unconnected-(IC5-QO13-Pad64)") (class "Default")
      (node (ref "IC5") (pin "64") (pinfunction "QO13_64") (pintype "bidirectional"))
    )
    (net (code "153") (name "unconnected-(IC5-QO14-Pad65)") (class "Default")
      (node (ref "IC5") (pin "65") (pinfunction "QO14_65") (pintype "bidirectional"))
    )
    (net (code "154") (name "unconnected-(IC5-QO15-Pad66)") (class "Default")
      (node (ref "IC5") (pin "66") (pinfunction "QO15_66") (pintype "bidirectional"))
    )
    (net (code "155") (name "unconnected-(IC5-QO16-Pad69)") (class "Default")
      (node (ref "IC5") (pin "69") (pinfunction "QO16_69") (pintype "bidirectional"))
    )
    (net (code "156") (name "unconnected-(IC5-QO17-Pad70)") (class "Default")
      (node (ref "IC5") (pin "70") (pinfunction "QO17_70") (pintype "bidirectional"))
    )
    (net (code "157") (name "unconnected-(IC5-QO18-Pad71)") (class "Default")
      (node (ref "IC5") (pin "71") (pinfunction "QO18_71") (pintype "bidirectional"))
    )
    (net (code "158") (name "unconnected-(IC5-QO19-Pad72)") (class "Default")
      (node (ref "IC5") (pin "72") (pinfunction "QO19_72") (pintype "bidirectional"))
    )
    (net (code "159") (name "unconnected-(IC5-QO20-Pad73)") (class "Default")
      (node (ref "IC5") (pin "73") (pinfunction "QO20_73") (pintype "bidirectional"))
    )
    (net (code "160") (name "unconnected-(IC5-QO21-Pad74)") (class "Default")
      (node (ref "IC5") (pin "74") (pinfunction "QO21_74") (pintype "bidirectional"))
    )
    (net (code "161") (name "unconnected-(IC5-QO22-Pad75)") (class "Default")
      (node (ref "IC5") (pin "75") (pinfunction "QO22_75") (pintype "bidirectional"))
    )
    (net (code "162") (name "unconnected-(IC5-QO23-Pad77)") (class "Default")
      (node (ref "IC5") (pin "77") (pinfunction "QO23_77") (pintype "bidirectional"))
    )
    (net (code "163") (name "unconnected-(IC5-SCDT-Pad8)") (class "Default")
      (node (ref "IC5") (pin "8") (pinfunction "SCDT_8") (pintype "bidirectional"))
    )
    (net (code "164") (name "unconnected-(IC5-~{PDO}-Pad9)") (class "Default")
      (node (ref "IC5") (pin "9") (pinfunction "~{PDO}_9") (pintype "bidirectional"))
    )
    (net (code "165") (name "unconnected-(IC5-~{PD}-Pad2)") (class "Default")
      (node (ref "IC5") (pin "2") (pinfunction "~{PD}_2") (pintype "bidirectional"))
    )
    (net (code "166") (name "unconnected-(IC6-(PCINT18{slash}INT0)PD2-Pad32)") (class "Default")
      (node (ref "IC6") (pin "32") (pinfunction "(PCINT18/INT0)PD2_32") (pintype "bidirectional"))
    )
    (net (code "167") (name "unconnected-(IC6-(PCINT19{slash}OC2B{slash}INT1)PD3-Pad1)") (class "Default")
      (node (ref "IC6") (pin "1") (pinfunction "(PCINT19/OC2B/INT1)PD3_1") (pintype "bidirectional"))
    )
    (net (code "168") (name "unconnected-(IC6-(PCINT20{slash}XCK{slash}T0)PD4-Pad2)") (class "Default")
      (node (ref "IC6") (pin "2") (pinfunction "(PCINT20/XCK/T0)PD4_2") (pintype "bidirectional"))
    )
    (net (code "169") (name "unconnected-(IC6-(PCINT21{slash}OC0B{slash}T1)PD5-Pad9)") (class "Default")
      (node (ref "IC6") (pin "9") (pinfunction "(PCINT21/OC0B/T1)PD5_9") (pintype "bidirectional"))
    )
    (net (code "170") (name "unconnected-(IC6-(PCINT22{slash}OC0A{slash}AIN0)PD6-Pad10)") (class "Default")
      (node (ref "IC6") (pin "10") (pinfunction "(PCINT22/OC0A/AIN0)PD6_10") (pintype "bidirectional"))
    )
    (net (code "171") (name "unconnected-(IC6-(PCINT23{slash}AIN1)PD7-Pad11)") (class "Default")
      (node (ref "IC6") (pin "11") (pinfunction "(PCINT23/AIN1)PD7_11") (pintype "bidirectional"))
    )
    (net (code "172") (name "unconnected-(IC6-ADC6-Pad19)") (class "Default")
      (node (ref "IC6") (pin "19") (pinfunction "ADC6_19") (pintype "bidirectional"))
    )
    (net (code "173") (name "unconnected-(IC6-ADC7-Pad22)") (class "Default")
      (node (ref "IC6") (pin "22") (pinfunction "ADC7_22") (pintype "bidirectional"))
    )
    (net (code "174") (name "unconnected-(IC6-PB0(PCINT0{slash}CLKO{slash}ICP1)-Pad12)") (class "Default")
      (node (ref "IC6") (pin "12") (pinfunction "PB0(PCINT0/CLKO/ICP1)_12") (pintype "bidirectional"))
    )
    (net (code "175") (name "unconnected-(IC6-PB2(SS{slash}OC1B{slash}PCINT2)-Pad14)") (class "Default")
      (node (ref "IC6") (pin "14") (pinfunction "PB2(SS/OC1B/PCINT2)_14") (pintype "bidirectional"))
    )
    (net (code "176") (name "unconnected-(IC6-PC1(ADC1{slash}PCINT9)-Pad24)") (class "Default")
      (node (ref "IC6") (pin "24") (pinfunction "PC1(ADC1/PCINT9)_24") (pintype "bidirectional"))
    )
    (net (code "177") (name "unconnected-(IC6-PC2(ADC2{slash}PCINT10)-Pad25)") (class "Default")
      (node (ref "IC6") (pin "25") (pinfunction "PC2(ADC2/PCINT10)_25") (pintype "bidirectional"))
    )
    (net (code "178") (name "unconnected-(IC6-PC3(ADC3{slash}PCINT11)-Pad26)") (class "Default")
      (node (ref "IC6") (pin "26") (pinfunction "PC3(ADC3/PCINT11)_26") (pintype "bidirectional"))
    )
    (net (code "179") (name "unconnected-(IC7-CBUS0-Pad23)") (class "Default")
      (node (ref "IC7") (pin "23") (pinfunction "CBUS0_23") (pintype "bidirectional"))
    )
    (net (code "180") (name "unconnected-(IC7-CBUS1-Pad22)") (class "Default")
      (node (ref "IC7") (pin "22") (pinfunction "CBUS1_22") (pintype "bidirectional"))
    )
    (net (code "181") (name "unconnected-(IC7-CBUS2-Pad13)") (class "Default")
      (node (ref "IC7") (pin "13") (pinfunction "CBUS2_13") (pintype "bidirectional"))
    )
    (net (code "182") (name "unconnected-(IC7-CBUS3-Pad14)") (class "Default")
      (node (ref "IC7") (pin "14") (pinfunction "CBUS3_14") (pintype "bidirectional"))
    )
    (net (code "183") (name "unconnected-(IC7-CBUS4-Pad12)") (class "Default")
      (node (ref "IC7") (pin "12") (pinfunction "CBUS4_12") (pintype "bidirectional"))
    )
    (net (code "184") (name "unconnected-(IC7-OSCI-Pad27)") (class "Default")
      (node (ref "IC7") (pin "27") (pinfunction "OSCI_27") (pintype "input"))
    )
    (net (code "185") (name "unconnected-(IC7-OSCO-Pad28)") (class "Default")
      (node (ref "IC7") (pin "28") (pinfunction "OSCO_28") (pintype "output"))
    )
    (net (code "186") (name "unconnected-(IC7-~{CTS}-Pad11)") (class "Default")
      (node (ref "IC7") (pin "11") (pinfunction "~{CTS}_11") (pintype "input"))
    )
    (net (code "187") (name "unconnected-(IC7-~{DCD}-Pad10)") (class "Default")
      (node (ref "IC7") (pin "10") (pinfunction "~{DCD}_10") (pintype "input"))
    )
    (net (code "188") (name "unconnected-(IC7-~{DSR}-Pad9)") (class "Default")
      (node (ref "IC7") (pin "9") (pinfunction "~{DSR}_9") (pintype "input"))
    )
    (net (code "189") (name "unconnected-(IC7-~{DTR}-Pad2)") (class "Default")
      (node (ref "IC7") (pin "2") (pinfunction "~{DTR}_2") (pintype "output"))
    )
    (net (code "190") (name "unconnected-(IC7-~{RI}-Pad6)") (class "Default")
      (node (ref "IC7") (pin "6") (pinfunction "~{RI}_6") (pintype "input"))
    )
    (net (code "191") (name "unconnected-(IC7-~{RTS}-Pad3)") (class "Default")
      (node (ref "IC7") (pin "3") (pinfunction "~{RTS}_3") (pintype "output"))
    )
    (net (code "192") (name "unconnected-(IC8-CLKIN-Pad31)") (class "Default")
      (node (ref "IC8") (pin "31") (pinfunction "CLKIN_31") (pintype "bidirectional"))
    )
    (net (code "193") (name "unconnected-(IC8-CLKSEL-Pad17)") (class "Default")
      (node (ref "IC8") (pin "17") (pinfunction "CLKSEL_17") (pintype "bidirectional"))
    )
    (net (code "194") (name "unconnected-(IC8-~{SHTDN}-Pad32)") (class "Default")
      (node (ref "IC8") (pin "32") (pinfunction "~{SHTDN}_32") (pintype "bidirectional"))
    )
  )
)
